# 03_-_SCHEMATIC.net
KiCad netlist of a schematic drawn in Altium Designer
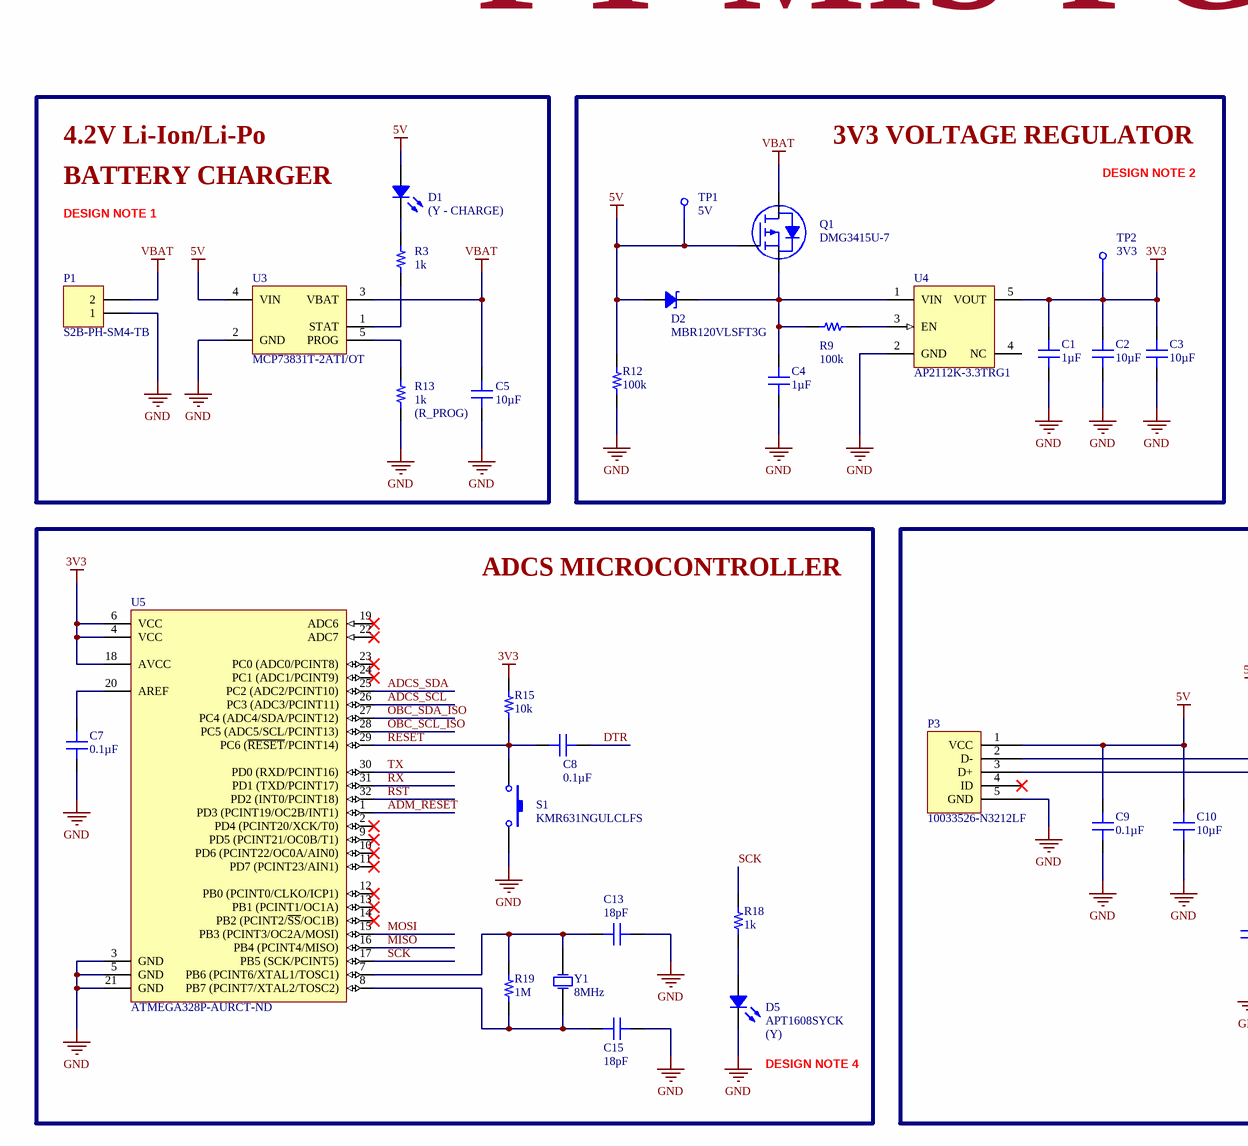
[diagram p0: [03] - SCHEMATIC.SchDoc, top left]
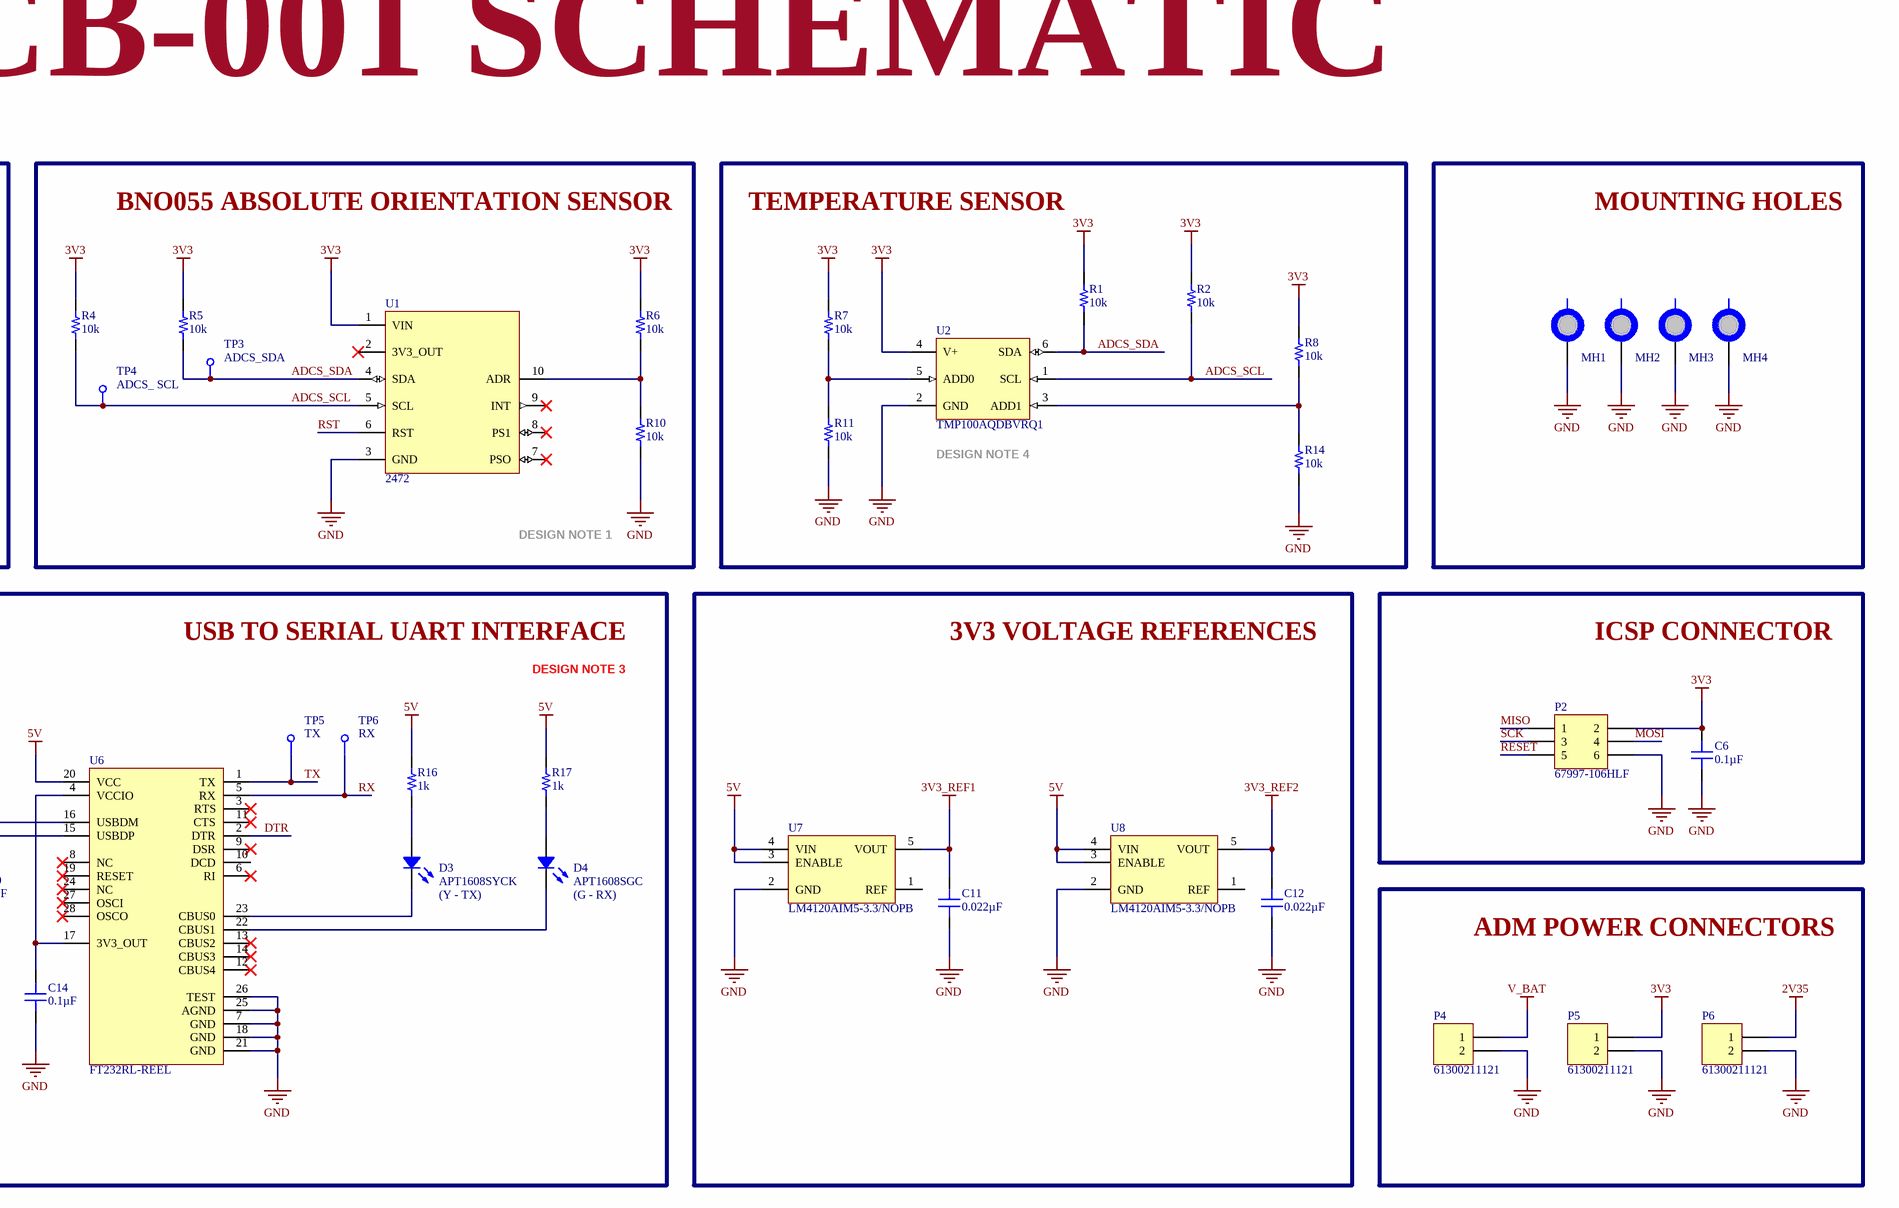
[diagram p1: [03] - SCHEMATIC.SchDoc, top right]
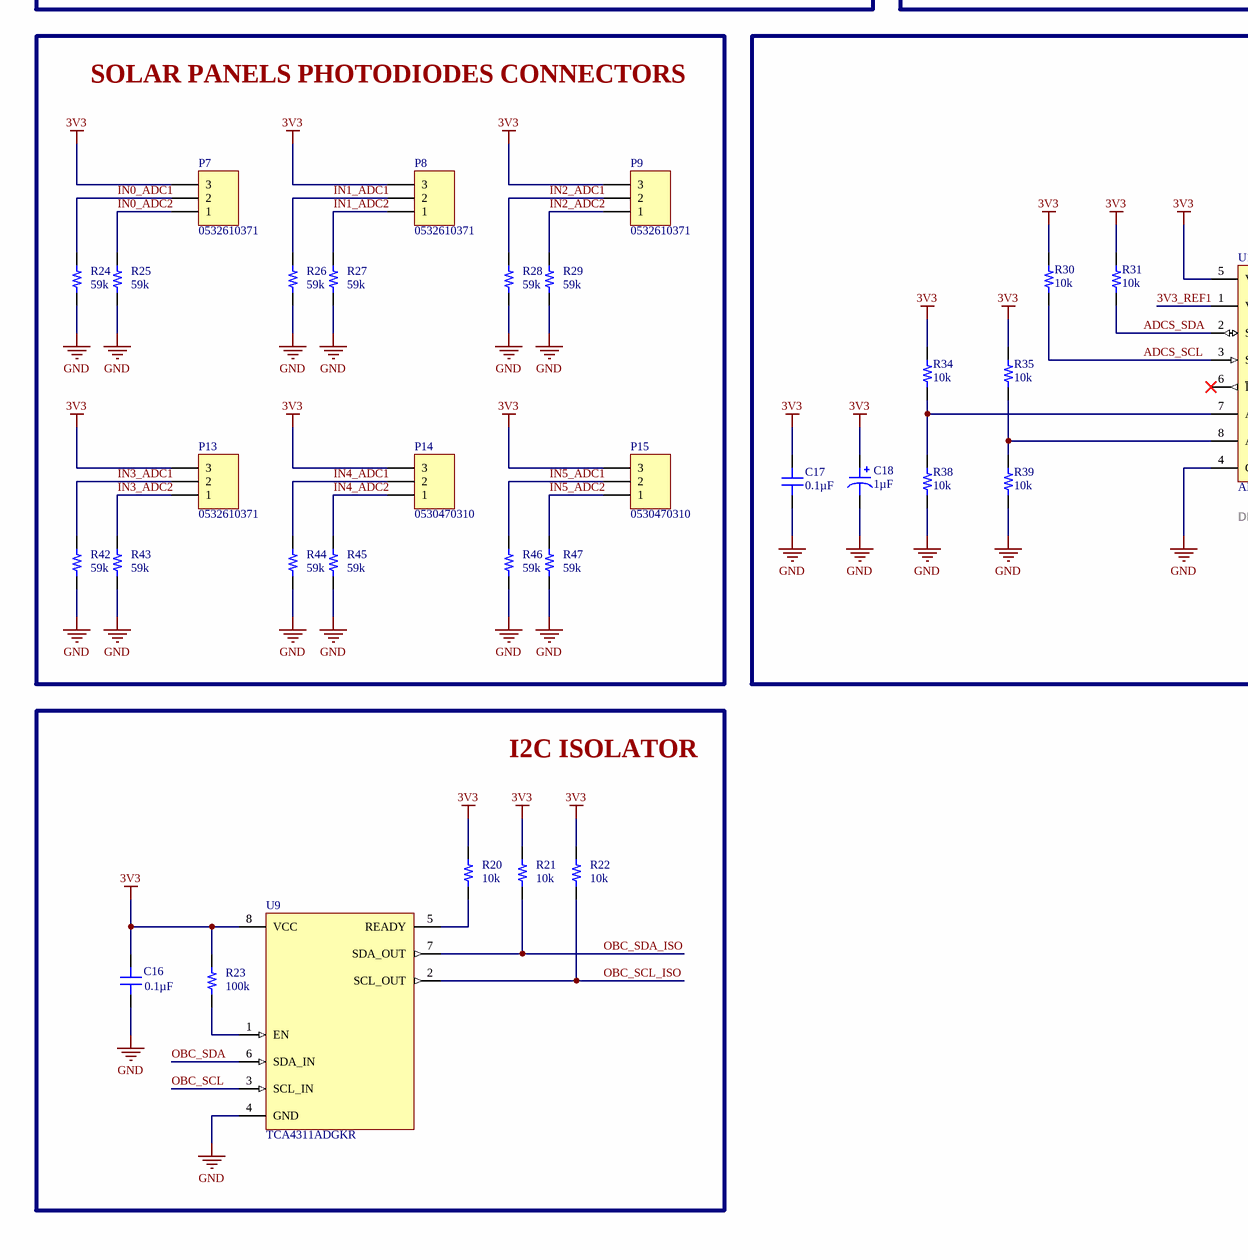
[diagram p2: [03] - SCHEMATIC.SchDoc, bottom left]
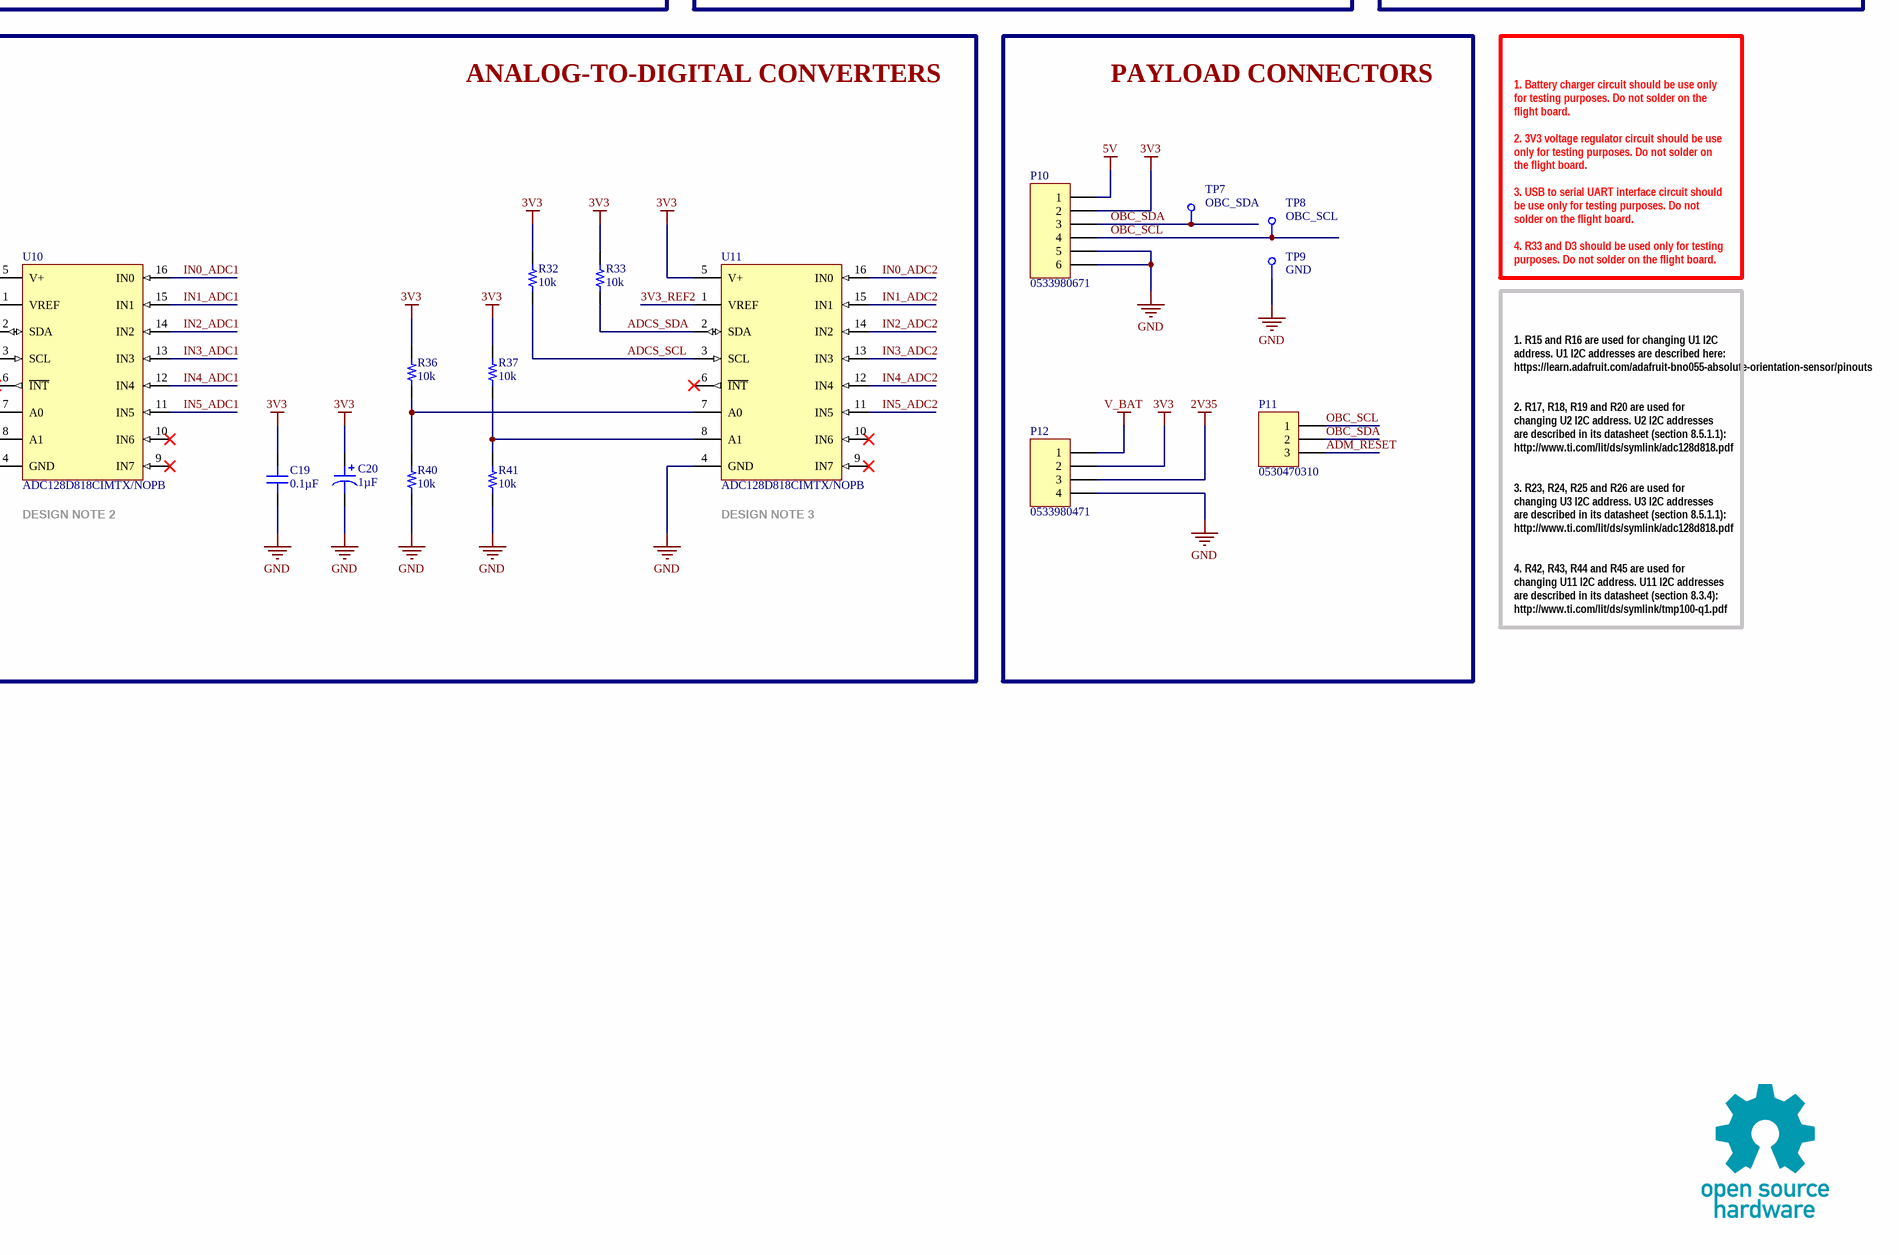
[diagram p3: [03] - SCHEMATIC.SchDoc, bottom right]

(export (version "E")
  (design (tool "Eeschema 10.0.6"))
  (components
    (comp (ref "C1")
      (value "CC0805KKX7R7BB105")
      (footprint "CAP 0805/2012")
      (description "CAP CER 1UF 16V X7R 0805")
      (fields
        (field (name "MANUFACTURER") "Yageo")
        (field (name "CAPACITANCE") "1µF")
        (field (name "TOLERANCE") "±10%")
      )
      (libsource (lib "UVG") (part "CC0805KKX7R7BB105"))
    )
    (comp (ref "C2")
      (value "LMK212BJ106KG-T")
      (footprint "CAP 0805/2012")
      (description "CAP CER 10UF 10V X5R 0805")
      (fields
        (field (name "MANUFACTURER") "Taiyo Yuden")
        (field (name "PCN PART NUMBER") "X5R, X7R Dielectrics 23/Jan/2008")
        (field (name "CAPACITANCE") "10µF")
      )
      (libsource (lib "UVG") (part "LMK212BJ106KG-T"))
    )
    (comp (ref "C3")
      (value "LMK212BJ106KG-T")
      (footprint "CAP 0805/2012")
      (description "CAP CER 10UF 10V X5R 0805")
      (fields
        (field (name "MANUFACTURER") "Taiyo Yuden")
        (field (name "PCN PART NUMBER") "X5R, X7R Dielectrics 23/Jan/2008")
        (field (name "CAPACITANCE") "10µF")
      )
      (libsource (lib "UVG") (part "LMK212BJ106KG-T"))
    )
    (comp (ref "C4")
      (value "CC0805KKX7R7BB105")
      (footprint "CAP 0805/2012")
      (description "CAP CER 1UF 16V X7R 0805")
      (fields
        (field (name "MANUFACTURER") "Yageo")
        (field (name "CAPACITANCE") "1µF")
        (field (name "TOLERANCE") "±10%")
      )
      (libsource (lib "UVG") (part "CC0805KKX7R7BB105"))
    )
    (comp (ref "C5")
      (value "LMK212BJ106KG-T")
      (footprint "CAP 0805/2012")
      (description "CAP CER 10UF 10V X5R 0805")
      (fields
        (field (name "MANUFACTURER") "Taiyo Yuden")
        (field (name "PCN PART NUMBER") "X5R, X7R Dielectrics 23/Jan/2008")
        (field (name "CAPACITANCE") "10µF")
      )
      (libsource (lib "UVG") (part "LMK212BJ106KG-T"))
    )
    (comp (ref "C6")
      (value "C2012X7R1H104K085AA")
      (footprint "CAP 0805/2012")
      (description "CAP CER 0.1UF 50V X7R 0805")
      (fields
        (field (name "MANUFACTURER") "TDK")
        (field (name "PCN PART NUMBER") "MLCC Part Number Change 30/Nov/2012")
        (field (name "CAPACITANCE") "0.1µF")
      )
      (libsource (lib "UVG") (part "C2012X7R1H104K085AA"))
    )
    (comp (ref "C7")
      (value "C2012X7R1H104K085AA")
      (footprint "CAP 0805/2012")
      (description "CAP CER 0.1UF 50V X7R 0805")
      (fields
        (field (name "MANUFACTURER") "TDK")
        (field (name "PCN PART NUMBER") "MLCC Part Number Change 30/Nov/2012")
        (field (name "CAPACITANCE") "0.1µF")
      )
      (libsource (lib "UVG") (part "C2012X7R1H104K085AA"))
    )
    (comp (ref "C8")
      (value "C2012X7R1H104K085AA")
      (footprint "CAP 0805/2012")
      (description "CAP CER 0.1UF 50V X7R 0805")
      (fields
        (field (name "MANUFACTURER") "TDK")
        (field (name "PCN PART NUMBER") "MLCC Part Number Change 30/Nov/2012")
        (field (name "CAPACITANCE") "0.1µF")
      )
      (libsource (lib "UVG") (part "C2012X7R1H104K085AA"))
    )
    (comp (ref "C9")
      (value "C0805C104Z3VACTU")
      (footprint "CAP 0805/2012")
      (description "Multilayer Ceramic Capacitors MLCC - SMD/SMT 25volts 0.1uF Y5V -20+80%")
      (fields
        (field (name "MANUFACTURER") "KEMET")
        (field (name "CAPACITANCE") "0.1µF")
        (field (name "TOLERANCE") "- 20 %, + 80 %")
      )
      (libsource (lib "UVG") (part "C0805C104Z3VACTU"))
    )
    (comp (ref "C10")
      (value "LMK212BJ106KG-T")
      (footprint "CAP 0805/2012")
      (description "CAP CER 10UF 10V X5R 0805")
      (fields
        (field (name "MANUFACTURER") "Taiyo Yuden")
        (field (name "PCN PART NUMBER") "X5R, X7R Dielectrics 23/Jan/2008")
        (field (name "CAPACITANCE") "10µF")
      )
      (libsource (lib "UVG") (part "LMK212BJ106KG-T"))
    )
    (comp (ref "C11")
      (value "GCM155R71H223KA55D")
      (footprint "CAP 0805/2012")
      (description "CAP CER 0.022UF 50V X7R 0402")
      (fields (field (name "MANUFACTURER") "Murata") (field (name "CAPACITANCE") "0.022µF"))
      (libsource (lib "UVG") (part "GCM155R71H223KA55D"))
    )
    (comp (ref "C12")
      (value "GCM155R71H223KA55D")
      (footprint "CAP 0805/2012")
      (description "CAP CER 0.022UF 50V X7R 0402")
      (fields (field (name "MANUFACTURER") "Murata") (field (name "CAPACITANCE") "0.022µF"))
      (libsource (lib "UVG") (part "GCM155R71H223KA55D"))
    )
    (comp (ref "C13")
      (value "C0805C180J5GAC-TU")
      (footprint "CAP 0805/2012")
      (description "CAP CER 18PF 50V NP0 0805")
      (fields
        (field (name "MANUFACTURER") "KEMET")
        (field (name "CAPACITANCE") "18pF")
        (field (name "VOLTAGE") "50VDC")
      )
      (libsource (lib "UVG") (part "C0805C180J5GAC-TU"))
    )
    (comp (ref "C14")
      (value "C0805C104Z3VACTU")
      (footprint "CAP 0805/2012")
      (description "Multilayer Ceramic Capacitors MLCC - SMD/SMT 25volts 0.1uF Y5V -20+80%")
      (fields
        (field (name "MANUFACTURER") "KEMET")
        (field (name "CAPACITANCE") "0.1µF")
        (field (name "TOLERANCE") "- 20 %, + 80 %")
      )
      (libsource (lib "UVG") (part "C0805C104Z3VACTU"))
    )
    (comp (ref "C15")
      (value "C0805C180J5GAC-TU")
      (footprint "CAP 0805/2012")
      (description "CAP CER 18PF 50V NP0 0805")
      (fields
        (field (name "MANUFACTURER") "KEMET")
        (field (name "CAPACITANCE") "18pF")
        (field (name "VOLTAGE") "50VDC")
      )
      (libsource (lib "UVG") (part "C0805C180J5GAC-TU"))
    )
    (comp (ref "C16")
      (value "C0805C104Z3VACTU")
      (footprint "CAP 0805/2012")
      (description "Multilayer Ceramic Capacitors MLCC - SMD/SMT 25volts 0.1uF Y5V -20+80%")
      (fields
        (field (name "MANUFACTURER") "KEMET")
        (field (name "CAPACITANCE") "0.1µF")
        (field (name "TOLERANCE") "- 20 %, + 80 %")
      )
      (libsource (lib "UVG") (part "C0805C104Z3VACTU"))
    )
    (comp (ref "C17")
      (value "C0805C104Z3VACTU")
      (footprint "CAP 0805/2012")
      (description "Multilayer Ceramic Capacitors MLCC - SMD/SMT 25volts 0.1uF Y5V -20+80%")
      (fields
        (field (name "MANUFACTURER") "KEMET")
        (field (name "CAPACITANCE") "0.1µF")
        (field (name "TOLERANCE") "- 20 %, + 80 %")
      )
      (libsource (lib "UVG") (part "C0805C104Z3VACTU"))
    )
    (comp (ref "C18")
      (value "F921C105MPA")
      (footprint "CAP 0805/2012 TANTALUM")
      (description "CAP TANT 1UF 16V 20% 0805")
      (fields (field (name "MANUFACTURER") "Kyocera AVX") (field (name "CAPACITANCE") "1µF"))
      (libsource (lib "UVG") (part "F921C105MPA"))
    )
    (comp (ref "C19")
      (value "C0805C104Z3VACTU")
      (footprint "CAP 0805/2012")
      (description "Multilayer Ceramic Capacitors MLCC - SMD/SMT 25volts 0.1uF Y5V -20+80%")
      (fields
        (field (name "MANUFACTURER") "KEMET")
        (field (name "CAPACITANCE") "0.1µF")
        (field (name "TOLERANCE") "- 20 %, + 80 %")
      )
      (libsource (lib "UVG") (part "C0805C104Z3VACTU"))
    )
    (comp (ref "C20")
      (value "F921C105MPA")
      (footprint "CAP 0805/2012 TANTALUM")
      (description "CAP TANT 1UF 16V 20% 0805")
      (fields (field (name "MANUFACTURER") "Kyocera AVX") (field (name "CAPACITANCE") "1µF"))
      (libsource (lib "UVG") (part "F921C105MPA"))
    )
    (comp (ref "D1")
      (value "APT1608SYCK")
      (footprint "LED 0603/1608 YELLOW")
      (description "LED 1.6X0.8MM 590NM YLW CLR SMD")
      (fields (field (name "MANUFACTURER") "Kingbright"))
      (libsource (lib "UVG") (part "APT1608SYCK"))
    )
    (comp (ref "D2")
      (value "MBR120VLSFT3G")
      (footprint "SOD123F")
      (description "Schottky Diodes & Rectifiers 1A 20V")
      (fields (field (name "MANUFACTURER") "ON Semiconductor"))
      (libsource (lib "UVG") (part "MBR120VLSFT3G"))
    )
    (comp (ref "D3")
      (value "APT1608SYCK")
      (footprint "LED 0603/1608 YELLOW")
      (description "LED 1.6X0.8MM 590NM YLW CLR SMD")
      (fields (field (name "MANUFACTURER") "Kingbright"))
      (libsource (lib "UVG") (part "APT1608SYCK"))
    )
    (comp (ref "D4")
      (value "APT1608SGC")
      (footprint "LED 0603/1608 GREEN")
      (description "LED 1.6X0.8MM 568NM GRN CLR SMD")
      (fields (field (name "MANUFACTURER") "Kingbright"))
      (libsource (lib "UVG") (part "APT1608SGC"))
    )
    (comp (ref "D5")
      (value "APT1608SYCK")
      (footprint "LED 0603/1608 YELLOW")
      (description "LED 1.6X0.8MM 590NM YLW CLR SMD")
      (fields (field (name "MANUFACTURER") "Kingbright"))
      (libsource (lib "UVG") (part "APT1608SYCK"))
    )
    (comp (ref "MH1")
      (value "MH_3.8MMNC_2.5MMD")
      (footprint "MH_3.8MMNC_2.5MMD_NON_COPPER_NPTH")
      (description "Mounting Hole 3.8mm Diameter (Non Copper), 2.5mm Drill NPTH")
      (libsource (lib "UVG") (part "MH_3.8MMNC_2MMD"))
    )
    (comp (ref "MH2")
      (value "MH_3.8MMNC_2.5MMD")
      (footprint "MH_3.8MMNC_2.5MMD_NON_COPPER_NPTH")
      (description "Mounting Hole 3.8mm Diameter (Non Copper), 2.5mm Drill NPTH")
      (libsource (lib "UVG") (part "MH_3.8MMNC_2MMD"))
    )
    (comp (ref "MH3")
      (value "MH_3.8MMNC_2.5MMD")
      (footprint "MH_3.8MMNC_2.5MMD_NON_COPPER_NPTH")
      (description "Mounting Hole 3.8mm Diameter (Non Copper), 2.5mm Drill NPTH")
      (libsource (lib "UVG") (part "MH_3.8MMNC_2MMD"))
    )
    (comp (ref "MH4")
      (value "MH_3.8MMNC_2.5MMD")
      (footprint "MH_3.8MMNC_2.5MMD_NON_COPPER_NPTH")
      (description "Mounting Hole 3.8mm Diameter (Non Copper), 2.5mm Drill NPTH")
      (libsource (lib "UVG") (part "MH_3.8MMNC_2MMD"))
    )
    (comp (ref "P1")
      (value "S2B-PH-SM4-TB")
      (footprint "S2B-PH-SM4-TB(LF)(SN)")
      (description "2 Positions Header, Shrouded Connector 0.079\" (2.00mm) Surface Mount, Right Angle Tin")
      (fields
        (field (name "MANUFACTURER") "JST")
        (field (name "MANUFACTURER PART NUMBER") "S2B-PH-SM4-TB(LF)(SN)")
      )
      (libsource (lib "UVG") (part "S2B-PH-SM4-TB(LF)(SN)"))
    )
    (comp (ref "P2")
      (value "67997-106HLF")
      (footprint "67997-106HLF")
      (description "6 Positions Header, Unshrouded Connector 0.100\" (2.54mm) Through Hole Gold or Gold, GXT™")
      (fields (field (name "MANUFACTURER") "Amphenol FCI"))
      (libsource (lib "UVG") (part "67997-106HLF"))
    )
    (comp (ref "P3")
      (value "10033526-N3212LF")
      (footprint "FCI USB 10033526-N3212LF")
      (description "Conn Mini USB Type B RCP 5 POS 0.8mm Solder RA SMD 5 Terminal 1 Port T/R")
      (fields (field (name "MANUFACTURER") "Amphenol FCI"))
      (libsource (lib "UVG") (part "10033526-N3212LF"))
    )
    (comp (ref "P4")
      (value "61300211121")
      (footprint "61300211121")
      (description "Headers & Wire Housings WR-PHD 2.54mm Header 2P THT")
      (fields (field (name "MANUFACTURER") "Wurth Electronics"))
      (libsource (lib "UVG") (part "61300211121"))
    )
    (comp (ref "P5")
      (value "61300211121")
      (footprint "61300211121")
      (description "Headers & Wire Housings WR-PHD 2.54mm Header 2P THT")
      (fields (field (name "MANUFACTURER") "Wurth Electronics"))
      (libsource (lib "UVG") (part "61300211121"))
    )
    (comp (ref "P6")
      (value "61300211121")
      (footprint "61300211121")
      (description "Headers & Wire Housings WR-PHD 2.54mm Header 2P THT")
      (fields (field (name "MANUFACTURER") "Wurth Electronics"))
      (libsource (lib "UVG") (part "61300211121"))
    )
    (comp (ref "P7")
      (value "0532610371")
      (footprint "0532610371")
      (description "3 Positions Header, Shrouded Connector 0.049\" (1.25mm) Surface Mount, Right Angle Tin")
      (fields (field (name "MANUFACTURER") "Molex"))
      (libsource (lib "UVG") (part "0532610371"))
    )
    (comp (ref "P8")
      (value "0532610371")
      (footprint "0532610371")
      (description "3 Positions Header, Shrouded Connector 0.049\" (1.25mm) Surface Mount, Right Angle Tin")
      (fields (field (name "MANUFACTURER") "Molex"))
      (libsource (lib "UVG") (part "0532610371"))
    )
    (comp (ref "P9")
      (value "0532610371")
      (footprint "0532610371")
      (description "3 Positions Header, Shrouded Connector 0.049\" (1.25mm) Surface Mount, Right Angle Tin")
      (fields (field (name "MANUFACTURER") "Molex"))
      (libsource (lib "UVG") (part "0532610371"))
    )
    (comp (ref "P10")
      (value "0533980671")
      (footprint "0533980671")
      (description "6 Positions Header, Shrouded Connector 0.049\" (1.25mm) Surface Mount, Right Angle Tin")
      (fields (field (name "MANUFACTURER") "Molex") (field (name "MANUFACTURER PART NUMBER") "53398-0671"))
      (libsource (lib "UVG") (part "0533980671"))
    )
    (comp (ref "P11")
      (value "0530470310")
      (footprint "0530470310")
      (description "CONN HEADER 3POS 1.25MM VERT TIN")
      (fields (field (name "MANUFACTURER") "Molex"))
      (libsource (lib "") (part "0530470310_1"))
    )
    (comp (ref "P12")
      (value "0533980471")
      (footprint "0533980471")
      (description "4 Positions Header, Shrouded Connector 0.049\" (1.25mm) Surface Mount, Right Angle Tin")
      (fields (field (name "MANUFACTURER") "Molex") (field (name "MANUFACTURER PART NUMBER") "53398-0471"))
      (libsource (lib "UVG") (part "0533980471"))
    )
    (comp (ref "P13")
      (value "0532610371")
      (footprint "0532610371")
      (description "3 Positions Header, Shrouded Connector 0.049\" (1.25mm) Surface Mount, Right Angle Tin")
      (fields (field (name "MANUFACTURER") "Molex"))
      (libsource (lib "UVG") (part "0532610371"))
    )
    (comp (ref "P14")
      (value "0530470310")
      (footprint "0530470310")
      (description "Conn Wire to Board HDR 3 POS 1.25mm Solder ST Thru-Hole PicoBlade™ Tray")
      (fields (field (name "MANUFACTURER") "Molex"))
      (libsource (lib "UVG") (part "0530470310"))
    )
    (comp (ref "P15")
      (value "0530470310")
      (footprint "0530470310")
      (description "Conn Wire to Board HDR 3 POS 1.25mm Solder ST Thru-Hole PicoBlade™ Tray")
      (fields (field (name "MANUFACTURER") "Molex"))
      (libsource (lib "UVG") (part "0530470310"))
    )
    (comp (ref "Q1")
      (value "DMG3415U-7")
      (footprint "DIODES SOT-23-3")
      (description "MOSFET P-CH 20V 4A SOT-23")
      (fields (field (name "MANUFACTURER") "Diodes"))
      (libsource (lib "UVG") (part "DMG3415U-7"))
    )
    (comp (ref "R1")
      (value "RC0805FR-0710KL")
      (footprint "RES 0805/2012")
      (description "RES SMD 10K OHM 1% 1/8W 0805")
      (fields
        (field (name "MANUFACTURER") "Yageo")
        (field (name "RESISTANCE") "10k")
        (field (name "TOLERANCE") "1 %")
      )
      (libsource (lib "UVG") (part "RC0805FR-0710KL"))
    )
    (comp (ref "R2")
      (value "RC0805FR-0710KL")
      (footprint "RES 0805/2012")
      (description "RES SMD 10K OHM 1% 1/8W 0805")
      (fields
        (field (name "MANUFACTURER") "Yageo")
        (field (name "RESISTANCE") "10k")
        (field (name "TOLERANCE") "1 %")
      )
      (libsource (lib "UVG") (part "RC0805FR-0710KL"))
    )
    (comp (ref "R3")
      (value "RNCP0805FTD1K00")
      (footprint "RES 0805/2012")
      (description "RNCP 0805 0.25W 1kO ±1% ±100ppm/°C High Power Anti-Sulfur ThinFilm Chip Resistor")
      (fields
        (field (name "MANUFACTURER") "Stackpole Electronics")
        (field (name "RESISTANCE (OHMS)") "1k")
        (field (name "TOLERANCE") "±1%")
      )
      (libsource (lib "UVG") (part "RNCP0805FTD1K00"))
    )
    (comp (ref "R4")
      (value "RR1220P-103-D")
      (footprint "RES 0805/2012")
      (description "RES SMD 10K OHM 0.5% 1/10W 0805")
      (fields
        (field (name "MANUFACTURER") "Susumu")
        (field (name "RESISTANCE") "10k")
        (field (name "TOLERANCE") "0.5 %")
      )
      (libsource (lib "UVG") (part "RR1220P-103-D"))
    )
    (comp (ref "R5")
      (value "RR1220P-103-D")
      (footprint "RES 0805/2012")
      (description "RES SMD 10K OHM 0.5% 1/10W 0805")
      (fields
        (field (name "MANUFACTURER") "Susumu")
        (field (name "RESISTANCE") "10k")
        (field (name "TOLERANCE") "0.5 %")
      )
      (libsource (lib "UVG") (part "RR1220P-103-D"))
    )
    (comp (ref "R6")
      (value "RR1220P-103-D")
      (footprint "RES 0805/2012")
      (description "RES SMD 10K OHM 0.5% 1/10W 0805")
      (fields
        (field (name "MANUFACTURER") "Susumu")
        (field (name "RESISTANCE") "10k")
        (field (name "TOLERANCE") "0.5 %")
      )
      (libsource (lib "UVG") (part "RR1220P-103-D"))
    )
    (comp (ref "R7")
      (value "RC0805FR-0710KL")
      (footprint "RES 0805/2012")
      (description "RES SMD 10K OHM 1% 1/8W 0805")
      (fields
        (field (name "MANUFACTURER") "Yageo")
        (field (name "RESISTANCE") "10k")
        (field (name "TOLERANCE") "1 %")
      )
      (libsource (lib "UVG") (part "RC0805FR-0710KL"))
    )
    (comp (ref "R8")
      (value "RC0805FR-0710KL")
      (footprint "RES 0805/2012")
      (description "RES SMD 10K OHM 1% 1/8W 0805")
      (fields
        (field (name "MANUFACTURER") "Yageo")
        (field (name "RESISTANCE") "10k")
        (field (name "TOLERANCE") "1 %")
      )
      (libsource (lib "UVG") (part "RC0805FR-0710KL"))
    )
    (comp (ref "R9")
      (value "RPC0805JT100K")
      (footprint "RES 0805/2012")
      (description "RES SMD 100K OHM 5% 1/4W 0805")
      (fields
        (field (name "MANUFACTURER") "Stackpole Electronics")
        (field (name "RESISTANCE (OHMS)") "100k")
        (field (name "TOLERANCE") "±5%")
      )
      (libsource (lib "UVG") (part "RPC0805JT100K"))
    )
    (comp (ref "R10")
      (value "RR1220P-103-D")
      (footprint "RES 0805/2012")
      (description "RES SMD 10K OHM 0.5% 1/10W 0805")
      (fields
        (field (name "MANUFACTURER") "Susumu")
        (field (name "RESISTANCE") "10k")
        (field (name "TOLERANCE") "0.5 %")
      )
      (libsource (lib "UVG") (part "RR1220P-103-D"))
    )
    (comp (ref "R11")
      (value "RC0805FR-0710KL")
      (footprint "RES 0805/2012")
      (description "RES SMD 10K OHM 1% 1/8W 0805")
      (fields
        (field (name "MANUFACTURER") "Yageo")
        (field (name "RESISTANCE") "10k")
        (field (name "TOLERANCE") "1 %")
      )
      (libsource (lib "UVG") (part "RC0805FR-0710KL"))
    )
    (comp (ref "R12")
      (value "RPC0805JT100K")
      (footprint "RES 0805/2012")
      (description "RES SMD 100K OHM 5% 1/4W 0805")
      (fields
        (field (name "MANUFACTURER") "Stackpole Electronics")
        (field (name "RESISTANCE (OHMS)") "100k")
        (field (name "TOLERANCE") "±5%")
      )
      (libsource (lib "UVG") (part "RPC0805JT100K"))
    )
    (comp (ref "R13")
      (value "RNCP0805FTD1K00")
      (footprint "RES 0805/2012")
      (description "RNCP 0805 0.25W 1kO ±1% ±100ppm/°C High Power Anti-Sulfur ThinFilm Chip Resistor")
      (fields
        (field (name "MANUFACTURER") "Stackpole Electronics")
        (field (name "RESISTANCE (OHMS)") "1k")
        (field (name "TOLERANCE") "±1%")
      )
      (libsource (lib "UVG") (part "RNCP0805FTD1K00"))
    )
    (comp (ref "R14")
      (value "RC0805FR-0710KL")
      (footprint "RES 0805/2012")
      (description "RES SMD 10K OHM 1% 1/8W 0805")
      (fields
        (field (name "MANUFACTURER") "Yageo")
        (field (name "RESISTANCE") "10k")
        (field (name "TOLERANCE") "1 %")
      )
      (libsource (lib "UVG") (part "RC0805FR-0710KL"))
    )
    (comp (ref "R15")
      (value "RC0805FR-0710KL")
      (footprint "RES 0805/2012")
      (description "RES SMD 10K OHM 1% 1/8W 0805")
      (fields
        (field (name "MANUFACTURER") "Yageo")
        (field (name "RESISTANCE") "10k")
        (field (name "TOLERANCE") "1 %")
      )
      (libsource (lib "UVG") (part "RC0805FR-0710KL"))
    )
    (comp (ref "R16")
      (value "RNCP0805FTD1K00")
      (footprint "RES 0805/2012")
      (description "RNCP 0805 0.25W 1kO ±1% ±100ppm/°C High Power Anti-Sulfur ThinFilm Chip Resistor")
      (fields
        (field (name "MANUFACTURER") "Stackpole Electronics")
        (field (name "RESISTANCE (OHMS)") "1k")
        (field (name "TOLERANCE") "±1%")
      )
      (libsource (lib "UVG") (part "RNCP0805FTD1K00"))
    )
    (comp (ref "R17")
      (value "RNCP0805FTD1K00")
      (footprint "RES 0805/2012")
      (description "RNCP 0805 0.25W 1kO ±1% ±100ppm/°C High Power Anti-Sulfur ThinFilm Chip Resistor")
      (fields
        (field (name "MANUFACTURER") "Stackpole Electronics")
        (field (name "RESISTANCE (OHMS)") "1k")
        (field (name "TOLERANCE") "±1%")
      )
      (libsource (lib "UVG") (part "RNCP0805FTD1K00"))
    )
    (comp (ref "R18")
      (value "RNCP0805FTD1K00")
      (footprint "RES 0805/2012")
      (description "RNCP 0805 0.25W 1kO ±1% ±100ppm/°C High Power Anti-Sulfur ThinFilm Chip Resistor")
      (fields
        (field (name "MANUFACTURER") "Stackpole Electronics")
        (field (name "RESISTANCE (OHMS)") "1k")
        (field (name "TOLERANCE") "±1%")
      )
      (libsource (lib "UVG") (part "RNCP0805FTD1K00"))
    )
    (comp (ref "R19")
      (value "RC0805FR-0710ML")
      (footprint "RES 0805/2012")
      (fields
        (field (name "MANUFACTURER") "Yageo")
        (field (name "RESISTANCE") "1M")
        (field (name "TOLERANCE") "1 %")
      )
      (libsource (lib "UVG") (part "RC0805FR-0710ML"))
    )
    (comp (ref "R20")
      (value "RR1220P-103-D")
      (footprint "RES 0805/2012")
      (description "RES SMD 10K OHM 0.5% 1/10W 0805")
      (fields
        (field (name "MANUFACTURER") "Susumu")
        (field (name "RESISTANCE") "10k")
        (field (name "TOLERANCE") "0.5 %")
      )
      (libsource (lib "UVG") (part "RR1220P-103-D"))
    )
    (comp (ref "R21")
      (value "RR1220P-103-D")
      (footprint "RES 0805/2012")
      (description "RES SMD 10K OHM 0.5% 1/10W 0805")
      (fields
        (field (name "MANUFACTURER") "Susumu")
        (field (name "RESISTANCE") "10k")
        (field (name "TOLERANCE") "0.5 %")
      )
      (libsource (lib "UVG") (part "RR1220P-103-D"))
    )
    (comp (ref "R22")
      (value "RR1220P-103-D")
      (footprint "RES 0805/2012")
      (description "RES SMD 10K OHM 0.5% 1/10W 0805")
      (fields
        (field (name "MANUFACTURER") "Susumu")
        (field (name "RESISTANCE") "10k")
        (field (name "TOLERANCE") "0.5 %")
      )
      (libsource (lib "UVG") (part "RR1220P-103-D"))
    )
    (comp (ref "R23")
      (value "RPC0805JT100K")
      (footprint "RES 0805/2012")
      (description "RES SMD 100K OHM 5% 1/4W 0805")
      (fields
        (field (name "MANUFACTURER") "Stackpole Electronics")
        (field (name "RESISTANCE (OHMS)") "100k")
        (field (name "TOLERANCE") "±5%")
      )
      (libsource (lib "UVG") (part "RPC0805JT100K"))
    )
    (comp (ref "R24")
      (value "ERA6AEB5902V")
      (footprint "RES 0805/2012")
      (description "RES SMD 59K OHM 0.1% 1/8W 0805")
      (fields
        (field (name "MANUFACTURER") "Panasonic")
        (field (name "RESISTANCE") "59k")
        (field (name "TOLERANCE") "0.1%")
      )
      (libsource (lib "UVG") (part "ERA6AEB5902V"))
    )
    (comp (ref "R25")
      (value "ERA6AEB5902V")
      (footprint "RES 0805/2012")
      (description "RES SMD 59K OHM 0.1% 1/8W 0805")
      (fields
        (field (name "MANUFACTURER") "Panasonic")
        (field (name "RESISTANCE") "59k")
        (field (name "TOLERANCE") "0.1%")
      )
      (libsource (lib "UVG") (part "ERA6AEB5902V"))
    )
    (comp (ref "R26")
      (value "ERA6AEB5902V")
      (footprint "RES 0805/2012")
      (description "RES SMD 59K OHM 0.1% 1/8W 0805")
      (fields
        (field (name "MANUFACTURER") "Panasonic")
        (field (name "RESISTANCE") "59k")
        (field (name "TOLERANCE") "0.1%")
      )
      (libsource (lib "UVG") (part "ERA6AEB5902V"))
    )
    (comp (ref "R27")
      (value "ERA6AEB5902V")
      (footprint "RES 0805/2012")
      (description "RES SMD 59K OHM 0.1% 1/8W 0805")
      (fields
        (field (name "MANUFACTURER") "Panasonic")
        (field (name "RESISTANCE") "59k")
        (field (name "TOLERANCE") "0.1%")
      )
      (libsource (lib "UVG") (part "ERA6AEB5902V"))
    )
    (comp (ref "R28")
      (value "ERA6AEB5902V")
      (footprint "RES 0805/2012")
      (description "RES SMD 59K OHM 0.1% 1/8W 0805")
      (fields
        (field (name "MANUFACTURER") "Panasonic")
        (field (name "RESISTANCE") "59k")
        (field (name "TOLERANCE") "0.1%")
      )
      (libsource (lib "UVG") (part "ERA6AEB5902V"))
    )
    (comp (ref "R29")
      (value "ERA6AEB5902V")
      (footprint "RES 0805/2012")
      (description "RES SMD 59K OHM 0.1% 1/8W 0805")
      (fields
        (field (name "MANUFACTURER") "Panasonic")
        (field (name "RESISTANCE") "59k")
        (field (name "TOLERANCE") "0.1%")
      )
      (libsource (lib "UVG") (part "ERA6AEB5902V"))
    )
    (comp (ref "R30")
      (value "RR1220P-103-D")
      (footprint "RES 0805/2012")
      (description "RES SMD 10K OHM 0.5% 1/10W 0805")
      (fields
        (field (name "MANUFACTURER") "Susumu")
        (field (name "RESISTANCE") "10k")
        (field (name "TOLERANCE") "0.5 %")
      )
      (libsource (lib "UVG") (part "RR1220P-103-D"))
    )
    (comp (ref "R31")
      (value "RR1220P-103-D")
      (footprint "RES 0805/2012")
      (description "RES SMD 10K OHM 0.5% 1/10W 0805")
      (fields
        (field (name "MANUFACTURER") "Susumu")
        (field (name "RESISTANCE") "10k")
        (field (name "TOLERANCE") "0.5 %")
      )
      (libsource (lib "UVG") (part "RR1220P-103-D"))
    )
    (comp (ref "R32")
      (value "RR1220P-103-D")
      (footprint "RES 0805/2012")
      (description "RES SMD 10K OHM 0.5% 1/10W 0805")
      (fields
        (field (name "MANUFACTURER") "Susumu")
        (field (name "RESISTANCE") "10k")
        (field (name "TOLERANCE") "0.5 %")
      )
      (libsource (lib "UVG") (part "RR1220P-103-D"))
    )
    (comp (ref "R33")
      (value "RR1220P-103-D")
      (footprint "RES 0805/2012")
      (description "RES SMD 10K OHM 0.5% 1/10W 0805")
      (fields
        (field (name "MANUFACTURER") "Susumu")
        (field (name "RESISTANCE") "10k")
        (field (name "TOLERANCE") "0.5 %")
      )
      (libsource (lib "UVG") (part "RR1220P-103-D"))
    )
    (comp (ref "R34")
      (value "RR1220P-103-D")
      (footprint "RES 0805/2012")
      (description "RES SMD 10K OHM 0.5% 1/10W 0805")
      (fields
        (field (name "MANUFACTURER") "Susumu")
        (field (name "RESISTANCE") "10k")
        (field (name "TOLERANCE") "0.5 %")
      )
      (libsource (lib "UVG") (part "RR1220P-103-D"))
    )
    (comp (ref "R35")
      (value "RR1220P-103-D")
      (footprint "RES 0805/2012")
      (description "RES SMD 10K OHM 0.5% 1/10W 0805")
      (fields
        (field (name "MANUFACTURER") "Susumu")
        (field (name "RESISTANCE") "10k")
        (field (name "TOLERANCE") "0.5 %")
      )
      (libsource (lib "UVG") (part "RR1220P-103-D"))
    )
    (comp (ref "R36")
      (value "RR1220P-103-D")
      (footprint "RES 0805/2012")
      (description "RES SMD 10K OHM 0.5% 1/10W 0805")
      (fields
        (field (name "MANUFACTURER") "Susumu")
        (field (name "RESISTANCE") "10k")
        (field (name "TOLERANCE") "0.5 %")
      )
      (libsource (lib "UVG") (part "RR1220P-103-D"))
    )
    (comp (ref "R37")
      (value "RR1220P-103-D")
      (footprint "RES 0805/2012")
      (description "RES SMD 10K OHM 0.5% 1/10W 0805")
      (fields
        (field (name "MANUFACTURER") "Susumu")
        (field (name "RESISTANCE") "10k")
        (field (name "TOLERANCE") "0.5 %")
      )
      (libsource (lib "UVG") (part "RR1220P-103-D"))
    )
    (comp (ref "R38")
      (value "RR1220P-103-D")
      (footprint "RES 0805/2012")
      (description "RES SMD 10K OHM 0.5% 1/10W 0805")
      (fields
        (field (name "MANUFACTURER") "Susumu")
        (field (name "RESISTANCE") "10k")
        (field (name "TOLERANCE") "0.5 %")
      )
      (libsource (lib "UVG") (part "RR1220P-103-D"))
    )
    (comp (ref "R39")
      (value "RR1220P-103-D")
      (footprint "RES 0805/2012")
      (description "RES SMD 10K OHM 0.5% 1/10W 0805")
      (fields
        (field (name "MANUFACTURER") "Susumu")
        (field (name "RESISTANCE") "10k")
        (field (name "TOLERANCE") "0.5 %")
      )
      (libsource (lib "UVG") (part "RR1220P-103-D"))
    )
    (comp (ref "R40")
      (value "RR1220P-103-D")
      (footprint "RES 0805/2012")
      (description "RES SMD 10K OHM 0.5% 1/10W 0805")
      (fields
        (field (name "MANUFACTURER") "Susumu")
        (field (name "RESISTANCE") "10k")
        (field (name "TOLERANCE") "0.5 %")
      )
      (libsource (lib "UVG") (part "RR1220P-103-D"))
    )
    (comp (ref "R41")
      (value "RR1220P-103-D")
      (footprint "RES 0805/2012")
      (description "RES SMD 10K OHM 0.5% 1/10W 0805")
      (fields
        (field (name "MANUFACTURER") "Susumu")
        (field (name "RESISTANCE") "10k")
        (field (name "TOLERANCE") "0.5 %")
      )
      (libsource (lib "UVG") (part "RR1220P-103-D"))
    )
    (comp (ref "R42")
      (value "ERA6AEB5902V")
      (footprint "RES 0805/2012")
      (description "RES SMD 59K OHM 0.1% 1/8W 0805")
      (fields
        (field (name "MANUFACTURER") "Panasonic")
        (field (name "RESISTANCE") "59k")
        (field (name "TOLERANCE") "0.1%")
      )
      (libsource (lib "UVG") (part "ERA6AEB5902V"))
    )
    (comp (ref "R43")
      (value "ERA6AEB5902V")
      (footprint "RES 0805/2012")
      (description "RES SMD 59K OHM 0.1% 1/8W 0805")
      (fields
        (field (name "MANUFACTURER") "Panasonic")
        (field (name "RESISTANCE") "59k")
        (field (name "TOLERANCE") "0.1%")
      )
      (libsource (lib "UVG") (part "ERA6AEB5902V"))
    )
    (comp (ref "R44")
      (value "ERA6AEB5902V")
      (footprint "RES 0805/2012")
      (description "RES SMD 59K OHM 0.1% 1/8W 0805")
      (fields
        (field (name "MANUFACTURER") "Panasonic")
        (field (name "RESISTANCE") "59k")
        (field (name "TOLERANCE") "0.1%")
      )
      (libsource (lib "UVG") (part "ERA6AEB5902V"))
    )
    (comp (ref "R45")
      (value "ERA6AEB5902V")
      (footprint "RES 0805/2012")
      (description "RES SMD 59K OHM 0.1% 1/8W 0805")
      (fields
        (field (name "MANUFACTURER") "Panasonic")
        (field (name "RESISTANCE") "59k")
        (field (name "TOLERANCE") "0.1%")
      )
      (libsource (lib "UVG") (part "ERA6AEB5902V"))
    )
    (comp (ref "R46")
      (value "ERA6AEB5902V")
      (footprint "RES 0805/2012")
      (description "RES SMD 59K OHM 0.1% 1/8W 0805")
      (fields
        (field (name "MANUFACTURER") "Panasonic")
        (field (name "RESISTANCE") "59k")
        (field (name "TOLERANCE") "0.1%")
      )
      (libsource (lib "UVG") (part "ERA6AEB5902V"))
    )
    (comp (ref "R47")
      (value "ERA6AEB5902V")
      (footprint "RES 0805/2012")
      (description "RES SMD 59K OHM 0.1% 1/8W 0805")
      (fields
        (field (name "MANUFACTURER") "Panasonic")
        (field (name "RESISTANCE") "59k")
        (field (name "TOLERANCE") "0.1%")
      )
      (libsource (lib "UVG") (part "ERA6AEB5902V"))
    )
    (comp (ref "S1")
      (value "KMR631NGULCLFS")
      (footprint "KMR631NGLFS")
      (description "SWITCH TACTILE SPST-NO 50MA 32V")
      (fields (field (name "MANUFACTURER") "ITT C&K"))
      (libsource (lib "UVG") (part "KMR631NGULCLFS"))
    )
    (comp (ref "TP1") (value "5V") (footprint "Testpoint") (libsource (lib "UVG") (part "Testpoint")))
    (comp (ref "TP2") (value "3V3") (footprint "Testpoint") (libsource (lib "UVG") (part "Testpoint")))
    (comp (ref "TP3") (value "ADCS_SDA") (footprint "Testpoint") (libsource (lib "UVG") (part "Testpoint")))
    (comp (ref "TP4") (value "ADCS_ SCL") (footprint "Testpoint") (libsource (lib "UVG") (part "Testpoint")))
    (comp (ref "TP5") (value "TX") (footprint "Testpoint") (libsource (lib "UVG") (part "Testpoint")))
    (comp (ref "TP6") (value "RX") (footprint "Testpoint") (libsource (lib "UVG") (part "Testpoint")))
    (comp (ref "TP7") (value "OBC_SDA") (footprint "Testpoint") (libsource (lib "UVG") (part "Testpoint")))
    (comp (ref "TP8") (value "OBC_SCL") (footprint "Testpoint") (libsource (lib "UVG") (part "Testpoint")))
    (comp (ref "TP9") (value "GND") (footprint "Testpoint") (libsource (lib "UVG") (part "Testpoint")))
    (comp (ref "U1")
      (value "2472")
      (footprint "ADAFRUIT BNO055")
      (description "A 9-DOF A O IMU F B - BNO055")
      (fields
        (field (name "MANUFACTURER") "Adafruit Industries")
        (field (name "UTILIZED IC / PART") "BNO055")
      )
      (libsource (lib "UVG") (part "2472"))
    )
    (comp (ref "U2")
      (value "TMP100AQDBVRQ1")
      (footprint "SOT95P245X145-6N")
      (description "SENSOR DIGITAL -55C-125C SOT23-6")
      (fields (field (name "MANUFACTURER") "Texas Instruments"))
      (libsource (lib "UVG") (part "TMP100AQDBVRQ1"))
    )
    (comp (ref "U3")
      (value "MCP73831T-2ATI/OT")
      (footprint "SOT95P245X110-5N")
      (fields (field (name "MANUFACTURER") "Microchip"))
      (libsource (lib "UVG") (part "MCP73831T-2ATI/OT"))
    )
    (comp (ref "U4")
      (value "AP2112K-3.3TRG1")
      (footprint "DIODES SOT-23-5 W5")
      (description "IC REG LDO 3.3V 0.6A SOT25")
      (fields (field (name "MANUFACTURER") "Diodes"))
      (libsource (lib "UVG") (part "AP2112K-3.3TRG1"))
    )
    (comp (ref "U5")
      (value "ATMEGA328P-AURCT-ND")
      (footprint "32A_L")
      (description "MCU 8-bit ATmega AVR RISC 32KB Flash 2.5V/3.3V/5V 32-Pin TQFP T/R")
      (fields
        (field (name "MANUFACTURER") "Microchip / Atmel")
        (field (name "MANUFACTURER PART NUMBER") "ATMEGA328P-AUR")
      )
      (libsource (lib "UVG") (part "ATMEGA328P-AUR"))
    )
    (comp (ref "U6")
      (value "FT232RL-REEL")
      (footprint "SOP65P790X200-28N")
      (description "IC USB FS SERIAL UART 28-SSOP")
      (fields (field (name "MANUFACTURER") "FTDI") (field (name "VOLTAGE") "5V"))
      (libsource (lib "UVG") (part "FT232RL-REEL"))
    )
    (comp (ref "U7")
      (value "LM4120AIM5-3.3/NOPB")
      (footprint "SOT95P245X110-5N")
      (description "TEXAS INSTRUMENTS   LM4120AIM5-3.3/NOPB   VOLTAGE REF, SERIES, 3.3V, SOT-23-5")
      (fields (field (name "MANUFACTURER") "Texas Instruments") (field (name "TOLERANCE") "0.2%"))
      (libsource (lib "UVG") (part "LM4120AIM5-3.3/NOPB"))
    )
    (comp (ref "U8")
      (value "LM4120AIM5-3.3/NOPB")
      (footprint "SOT95P245X110-5N")
      (description "TEXAS INSTRUMENTS   LM4120AIM5-3.3/NOPB   VOLTAGE REF, SERIES, 3.3V, SOT-23-5")
      (fields (field (name "MANUFACTURER") "Texas Instruments") (field (name "TOLERANCE") "0.2%"))
      (libsource (lib "UVG") (part "LM4120AIM5-3.3/NOPB"))
    )
    (comp (ref "U9")
      (value "TCA4311ADGKR")
      (footprint "8-MSOP")
      (description "IC REDRIVER I2C HOTSWAP 8VSSOP")
      (fields (field (name "MANUFACTURER") "Texas Instruments"))
      (libsource (lib "UVG") (part "TCA4311ADGKR"))
    )
    (comp (ref "U10")
      (value "ADC128D818CIMTX/NOPB")
      (footprint "TSOP65P640X120-16N")
      (description "Analog to Digital Converters - ADC")
      (fields (field (name "MANUFACTURER") "TI National Semiconductor"))
      (libsource (lib "UVG") (part "ADC128D818CIMTX/NOPB"))
    )
    (comp (ref "U11")
      (value "ADC128D818CIMTX/NOPB")
      (footprint "TSOP65P640X120-16N")
      (description "Analog to Digital Converters - ADC")
      (fields (field (name "MANUFACTURER") "TI National Semiconductor"))
      (libsource (lib "UVG") (part "ADC128D818CIMTX/NOPB"))
    )
    (comp (ref "Y1")
      (value "8MHz")
      (footprint "ABM7-16.000MHZ-D2Y-T")
      (description "CRYSTAL 8.0000MHZ 18PF SMD")
      (fields
        (field (name "MANUFACTURER") "Abracon")
        (field (name "MANUFACTURER PART NUMBER") "ABM7-8.000MHZ-D2Y-T")
      )
      (libsource (lib "UVG") (part "ABM7-8.000MHZ-D2Y-T"))
    )
  )
  (nets
    (net (code "1") (name "/ADCS_SCL") (class "Default")
      (node (ref "R2") (pin "1") (pinfunction "1_1") (pintype "passive"))
      (node (ref "R30") (pin "2") (pinfunction "2_2") (pintype "passive"))
      (node (ref "R32") (pin "2") (pinfunction "2_2") (pintype "passive"))
      (node (ref "R4") (pin "2") (pinfunction "2_2") (pintype "passive"))
      (node (ref "TP4") (pin "1") (pinfunction "1_1") (pintype "passive"))
      (node (ref "U1") (pin "5") (pinfunction "SCL_5") (pintype "input"))
      (node (ref "U10") (pin "3") (pinfunction "SCL_3") (pintype "input"))
      (node (ref "U11") (pin "3") (pinfunction "SCL_3") (pintype "input"))
      (node (ref "U2") (pin "1") (pinfunction "SCL_1") (pintype "input"))
      (node (ref "U5") (pin "26") (pinfunction "PC3_(ADC3/PCINT11)_26") (pintype "bidirectional"))
    )
    (net (code "2") (name "/ADCS_SDA") (class "Default")
      (node (ref "R1") (pin "1") (pinfunction "1_1") (pintype "passive"))
      (node (ref "R31") (pin "2") (pinfunction "2_2") (pintype "passive"))
      (node (ref "R33") (pin "2") (pinfunction "2_2") (pintype "passive"))
      (node (ref "R5") (pin "2") (pinfunction "2_2") (pintype "passive"))
      (node (ref "TP3") (pin "1") (pinfunction "1_1") (pintype "passive"))
      (node (ref "U1") (pin "4") (pinfunction "SDA_4") (pintype "bidirectional"))
      (node (ref "U10") (pin "2") (pinfunction "SDA_2") (pintype "bidirectional"))
      (node (ref "U11") (pin "2") (pinfunction "SDA_2") (pintype "bidirectional"))
      (node (ref "U2") (pin "6") (pinfunction "SDA_6") (pintype "bidirectional"))
      (node (ref "U5") (pin "25") (pinfunction "PC2_(ADC2/PCINT10)_25") (pintype "bidirectional"))
    )
    (net (code "3") (name "/ADM_RESET") (class "Default")
      (node (ref "P11") (pin "3") (pinfunction "3_3") (pintype "passive"))
      (node (ref "U5") (pin "1") (pinfunction "PD3_(PCINT19/OC2B/INT1)_1") (pintype "bidirectional"))
    )
    (net (code "4") (name "/DTR") (class "Default")
      (node (ref "C8") (pin "1") (pinfunction "1_1") (pintype "passive"))
      (node (ref "U6") (pin "2") (pinfunction "DTR_2") (pintype "passive"))
    )
    (net (code "5") (name "/IN0_ADC1") (class "Default")
      (node (ref "P7") (pin "2") (pinfunction "2_2") (pintype "passive"))
      (node (ref "R24") (pin "2") (pinfunction "2_2") (pintype "passive"))
      (node (ref "U10") (pin "16") (pinfunction "IN0_16") (pintype "input"))
    )
    (net (code "6") (name "/IN0_ADC2") (class "Default")
      (node (ref "P7") (pin "1") (pinfunction "1_1") (pintype "passive"))
      (node (ref "R25") (pin "2") (pinfunction "2_2") (pintype "passive"))
      (node (ref "U11") (pin "16") (pinfunction "IN0_16") (pintype "input"))
    )
    (net (code "7") (name "/IN1_ADC1") (class "Default")
      (node (ref "P8") (pin "2") (pinfunction "2_2") (pintype "passive"))
      (node (ref "R26") (pin "2") (pinfunction "2_2") (pintype "passive"))
      (node (ref "U10") (pin "15") (pinfunction "IN1_15") (pintype "input"))
    )
    (net (code "8") (name "/IN1_ADC2") (class "Default")
      (node (ref "P8") (pin "1") (pinfunction "1_1") (pintype "passive"))
      (node (ref "R27") (pin "2") (pinfunction "2_2") (pintype "passive"))
      (node (ref "U11") (pin "15") (pinfunction "IN1_15") (pintype "input"))
    )
    (net (code "9") (name "/IN2_ADC1") (class "Default")
      (node (ref "P9") (pin "2") (pinfunction "2_2") (pintype "passive"))
      (node (ref "R28") (pin "2") (pinfunction "2_2") (pintype "passive"))
      (node (ref "U10") (pin "14") (pinfunction "IN2_14") (pintype "input"))
    )
    (net (code "10") (name "/IN2_ADC2") (class "Default")
      (node (ref "P9") (pin "1") (pinfunction "1_1") (pintype "passive"))
      (node (ref "R29") (pin "2") (pinfunction "2_2") (pintype "passive"))
      (node (ref "U11") (pin "14") (pinfunction "IN2_14") (pintype "input"))
    )
    (net (code "11") (name "/IN3_ADC1") (class "Default")
      (node (ref "P13") (pin "2") (pinfunction "2_2") (pintype "passive"))
      (node (ref "R42") (pin "2") (pinfunction "2_2") (pintype "passive"))
      (node (ref "U10") (pin "13") (pinfunction "IN3_13") (pintype "input"))
    )
    (net (code "12") (name "/IN3_ADC2") (class "Default")
      (node (ref "P13") (pin "1") (pinfunction "1_1") (pintype "passive"))
      (node (ref "R43") (pin "2") (pinfunction "2_2") (pintype "passive"))
      (node (ref "U11") (pin "13") (pinfunction "IN3_13") (pintype "input"))
    )
    (net (code "13") (name "/IN4_ADC1") (class "Default")
      (node (ref "P14") (pin "2") (pinfunction "2_2") (pintype "passive"))
      (node (ref "R44") (pin "2") (pinfunction "2_2") (pintype "passive"))
      (node (ref "U10") (pin "12") (pinfunction "IN4_12") (pintype "input"))
    )
    (net (code "14") (name "/IN4_ADC2") (class "Default")
      (node (ref "P14") (pin "1") (pinfunction "1_1") (pintype "passive"))
      (node (ref "R45") (pin "2") (pinfunction "2_2") (pintype "passive"))
      (node (ref "U11") (pin "12") (pinfunction "IN4_12") (pintype "input"))
    )
    (net (code "15") (name "/IN5_ADC1") (class "Default")
      (node (ref "P15") (pin "2") (pinfunction "2_2") (pintype "passive"))
      (node (ref "R46") (pin "2") (pinfunction "2_2") (pintype "passive"))
      (node (ref "U10") (pin "11") (pinfunction "IN5_11") (pintype "input"))
    )
    (net (code "16") (name "/IN5_ADC2") (class "Default")
      (node (ref "P15") (pin "1") (pinfunction "1_1") (pintype "passive"))
      (node (ref "R47") (pin "2") (pinfunction "2_2") (pintype "passive"))
      (node (ref "U11") (pin "11") (pinfunction "IN5_11") (pintype "input"))
    )
    (net (code "17") (name "/MISO") (class "Default")
      (node (ref "P2") (pin "1") (pinfunction "1_1") (pintype "passive"))
      (node (ref "U5") (pin "16") (pinfunction "PB4_(PCINT4/MISO)_16") (pintype "bidirectional"))
    )
    (net (code "18") (name "/MOSI") (class "Default")
      (node (ref "P2") (pin "4") (pinfunction "4_4") (pintype "passive"))
      (node (ref "U5") (pin "15") (pinfunction "PB3_(PCINT3/OC2A/MOSI)_15") (pintype "bidirectional"))
    )
    (net (code "19") (name "/OBC_SCL") (class "Default")
      (node (ref "P10") (pin "4") (pinfunction "4_4") (pintype "passive"))
      (node (ref "P11") (pin "1") (pinfunction "1_1") (pintype "passive"))
      (node (ref "TP8") (pin "1") (pinfunction "1_1") (pintype "passive"))
      (node (ref "U9") (pin "3") (pinfunction "SCL_IN_3") (pintype "input"))
    )
    (net (code "20") (name "/OBC_SCL_ISO") (class "Default")
      (node (ref "R22") (pin "1") (pinfunction "1_1") (pintype "passive"))
      (node (ref "U5") (pin "28") (pinfunction "PC5_(ADC5/SCL/PCINT13)_28") (pintype "bidirectional"))
      (node (ref "U9") (pin "2") (pinfunction "SCL_OUT_2") (pintype "output"))
    )
    (net (code "21") (name "/OBC_SDA") (class "Default")
      (node (ref "P10") (pin "3") (pinfunction "3_3") (pintype "passive"))
      (node (ref "P11") (pin "2") (pinfunction "2_2") (pintype "passive"))
      (node (ref "TP7") (pin "1") (pinfunction "1_1") (pintype "passive"))
      (node (ref "U9") (pin "6") (pinfunction "SDA_IN_6") (pintype "input"))
    )
    (net (code "22") (name "/OBC_SDA_ISO") (class "Default")
      (node (ref "R21") (pin "1") (pinfunction "1_1") (pintype "passive"))
      (node (ref "U5") (pin "27") (pinfunction "PC4_(ADC4/SDA/PCINT12)_27") (pintype "bidirectional"))
      (node (ref "U9") (pin "7") (pinfunction "SDA_OUT_7") (pintype "output"))
    )
    (net (code "23") (name "/RESET") (class "Default")
      (node (ref "C8") (pin "2") (pinfunction "2_2") (pintype "passive"))
      (node (ref "P2") (pin "5") (pinfunction "5_5") (pintype "passive"))
      (node (ref "R15") (pin "1") (pinfunction "1_1") (pintype "passive"))
      (node (ref "S1") (pin "1") (pinfunction "1_1") (pintype "passive"))
      (node (ref "U5") (pin "29") (pinfunction "PC6_(~{RESET}/PCINT14)_29") (pintype "bidirectional"))
    )
    (net (code "24") (name "/RST") (class "Default")
      (node (ref "U1") (pin "6") (pinfunction "RST_6") (pintype "passive"))
      (node (ref "U5") (pin "32") (pinfunction "PD2_(INT0/PCINT18)_32") (pintype "bidirectional"))
    )
    (net (code "25") (name "/RX") (class "Default")
      (node (ref "TP6") (pin "1") (pinfunction "1_1") (pintype "passive"))
      (node (ref "U5") (pin "31") (pinfunction "PD1_(TXD/PCINT17)_31") (pintype "bidirectional"))
      (node (ref "U6") (pin "5") (pinfunction "RX_5") (pintype "passive"))
    )
    (net (code "26") (name "/SCK") (class "Default")
      (node (ref "P2") (pin "3") (pinfunction "3_3") (pintype "passive"))
      (node (ref "R18") (pin "1") (pinfunction "1_1") (pintype "passive"))
      (node (ref "U5") (pin "17") (pinfunction "PB5_(SCK/PCINT5)_17") (pintype "bidirectional"))
    )
    (net (code "27") (name "/TX") (class "Default")
      (node (ref "TP5") (pin "1") (pinfunction "1_1") (pintype "passive"))
      (node (ref "U5") (pin "30") (pinfunction "PD0_(RXD/PCINT16)_30") (pintype "bidirectional"))
      (node (ref "U6") (pin "1") (pinfunction "TX_1") (pintype "passive"))
    )
    (net (code "28") (name "2V35") (class "Default")
      (node (ref "P12") (pin "3") (pinfunction "3_3") (pintype "passive"))
      (node (ref "P6") (pin "1") (pinfunction "1_1") (pintype "passive"))
    )
    (net (code "29") (name "3V3") (class "Default")
      (node (ref "C1") (pin "1") (pinfunction "1_1") (pintype "passive"))
      (node (ref "C16") (pin "2") (pinfunction "2_2") (pintype "passive"))
      (node (ref "C17") (pin "2") (pinfunction "2_2") (pintype "passive"))
      (node (ref "C18") (pin "1") (pinfunction "1_1") (pintype "passive"))
      (node (ref "C19") (pin "2") (pinfunction "2_2") (pintype "passive"))
      (node (ref "C2") (pin "2") (pinfunction "2_2") (pintype "passive"))
      (node (ref "C20") (pin "1") (pinfunction "1_1") (pintype "passive"))
      (node (ref "C3") (pin "2") (pinfunction "2_2") (pintype "passive"))
      (node (ref "C6") (pin "2") (pinfunction "2_2") (pintype "passive"))
      (node (ref "P10") (pin "2") (pinfunction "2_2") (pintype "passive"))
      (node (ref "P12") (pin "2") (pinfunction "2_2") (pintype "passive"))
      (node (ref "P13") (pin "3") (pinfunction "3_3") (pintype "passive"))
      (node (ref "P14") (pin "3") (pinfunction "3_3") (pintype "passive"))
      (node (ref "P15") (pin "3") (pinfunction "3_3") (pintype "passive"))
      (node (ref "P2") (pin "2") (pinfunction "2_2") (pintype "passive"))
      (node (ref "P5") (pin "1") (pinfunction "1_1") (pintype "passive"))
      (node (ref "P7") (pin "3") (pinfunction "3_3") (pintype "passive"))
      (node (ref "P8") (pin "3") (pinfunction "3_3") (pintype "passive"))
      (node (ref "P9") (pin "3") (pinfunction "3_3") (pintype "passive"))
      (node (ref "R1") (pin "2") (pinfunction "2_2") (pintype "passive"))
      (node (ref "R15") (pin "2") (pinfunction "2_2") (pintype "passive"))
      (node (ref "R2") (pin "2") (pinfunction "2_2") (pintype "passive"))
      (node (ref "R20") (pin "2") (pinfunction "2_2") (pintype "passive"))
      (node (ref "R21") (pin "2") (pinfunction "2_2") (pintype "passive"))
      (node (ref "R22") (pin "2") (pinfunction "2_2") (pintype "passive"))
      (node (ref "R23") (pin "2") (pinfunction "2_2") (pintype "passive"))
      (node (ref "R30") (pin "1") (pinfunction "1_1") (pintype "passive"))
      (node (ref "R31") (pin "1") (pinfunction "1_1") (pintype "passive"))
      (node (ref "R32") (pin "1") (pinfunction "1_1") (pintype "passive"))
      (node (ref "R33") (pin "1") (pinfunction "1_1") (pintype "passive"))
      (node (ref "R34") (pin "2") (pinfunction "2_2") (pintype "passive"))
      (node (ref "R35") (pin "2") (pinfunction "2_2") (pintype "passive"))
      (node (ref "R36") (pin "2") (pinfunction "2_2") (pintype "passive"))
      (node (ref "R37") (pin "2") (pinfunction "2_2") (pintype "passive"))
      (node (ref "R4") (pin "1") (pinfunction "1_1") (pintype "passive"))
      (node (ref "R5") (pin "1") (pinfunction "1_1") (pintype "passive"))
      (node (ref "R6") (pin "1") (pinfunction "1_1") (pintype "passive"))
      (node (ref "R7") (pin "2") (pinfunction "2_2") (pintype "passive"))
      (node (ref "R8") (pin "2") (pinfunction "2_2") (pintype "passive"))
      (node (ref "TP2") (pin "1") (pinfunction "1_1") (pintype "passive"))
      (node (ref "U1") (pin "1") (pinfunction "VIN_1") (pintype "power_in"))
      (node (ref "U10") (pin "5") (pinfunction "V+_5") (pintype "power_in"))
      (node (ref "U11") (pin "5") (pinfunction "V+_5") (pintype "power_in"))
      (node (ref "U2") (pin "4") (pinfunction "V+_4") (pintype "power_in"))
      (node (ref "U4") (pin "5") (pinfunction "VOUT_5") (pintype "power_in"))
      (node (ref "U5") (pin "18") (pinfunction "AVCC_18") (pintype "power_in"))
      (node (ref "U5") (pin "4") (pinfunction "VCC_4") (pintype "power_in"))
      (node (ref "U5") (pin "6") (pinfunction "VCC_6") (pintype "power_in"))
      (node (ref "U9") (pin "8") (pinfunction "VCC_8") (pintype "power_in"))
    )
    (net (code "30") (name "3V3_REF1") (class "Default")
      (node (ref "C11") (pin "1") (pinfunction "1_1") (pintype "passive"))
      (node (ref "U10") (pin "1") (pinfunction "VREF_1") (pintype "power_in"))
      (node (ref "U7") (pin "5") (pinfunction "VOUT_5") (pintype "power_in"))
    )
    (net (code "31") (name "3V3_REF2") (class "Default")
      (node (ref "C12") (pin "1") (pinfunction "1_1") (pintype "passive"))
      (node (ref "U11") (pin "1") (pinfunction "VREF_1") (pintype "power_in"))
      (node (ref "U8") (pin "5") (pinfunction "VOUT_5") (pintype "power_in"))
    )
    (net (code "32") (name "5V") (class "Default")
      (node (ref "C10") (pin "2") (pinfunction "2_2") (pintype "passive"))
      (node (ref "C9") (pin "2") (pinfunction "2_2") (pintype "passive"))
      (node (ref "D1") (pin "1") (pinfunction "1_1") (pintype "passive"))
      (node (ref "D2") (pin "1") (pinfunction "1_1") (pintype "passive"))
      (node (ref "P10") (pin "1") (pinfunction "1_1") (pintype "passive"))
      (node (ref "P3") (pin "1") (pinfunction "VCC_1") (pintype "passive"))
      (node (ref "Q1") (pin "1") (pinfunction "G_1") (pintype "passive"))
      (node (ref "R12") (pin "2") (pinfunction "2_2") (pintype "passive"))
      (node (ref "R16") (pin "2") (pinfunction "2_2") (pintype "passive"))
      (node (ref "R17") (pin "2") (pinfunction "2_2") (pintype "passive"))
      (node (ref "TP1") (pin "1") (pinfunction "1_1") (pintype "passive"))
      (node (ref "U3") (pin "4") (pinfunction "VIN_4") (pintype "power_in"))
      (node (ref "U6") (pin "20") (pinfunction "VCC_20") (pintype "passive"))
      (node (ref "U7") (pin "3") (pinfunction "ENABLE_3") (pintype "passive"))
      (node (ref "U7") (pin "4") (pinfunction "VIN_4") (pintype "power_in"))
      (node (ref "U8") (pin "3") (pinfunction "ENABLE_3") (pintype "passive"))
      (node (ref "U8") (pin "4") (pinfunction "VIN_4") (pintype "power_in"))
    )
    (net (code "33") (name "GND") (class "Default")
      (node (ref "C1") (pin "2") (pinfunction "2_2") (pintype "passive"))
      (node (ref "C10") (pin "1") (pinfunction "1_1") (pintype "passive"))
      (node (ref "C11") (pin "2") (pinfunction "2_2") (pintype "passive"))
      (node (ref "C12") (pin "2") (pinfunction "2_2") (pintype "passive"))
      (node (ref "C13") (pin "1") (pinfunction "1_1") (pintype "passive"))
      (node (ref "C14") (pin "1") (pinfunction "1_1") (pintype "passive"))
      (node (ref "C15") (pin "1") (pinfunction "1_1") (pintype "passive"))
      (node (ref "C16") (pin "1") (pinfunction "1_1") (pintype "passive"))
      (node (ref "C17") (pin "1") (pinfunction "1_1") (pintype "passive"))
      (node (ref "C18") (pin "2") (pinfunction "2_2") (pintype "passive"))
      (node (ref "C19") (pin "1") (pinfunction "1_1") (pintype "passive"))
      (node (ref "C2") (pin "1") (pinfunction "1_1") (pintype "passive"))
      (node (ref "C20") (pin "2") (pinfunction "2_2") (pintype "passive"))
      (node (ref "C3") (pin "1") (pinfunction "1_1") (pintype "passive"))
      (node (ref "C4") (pin "2") (pinfunction "2_2") (pintype "passive"))
      (node (ref "C5") (pin "1") (pinfunction "1_1") (pintype "passive"))
      (node (ref "C6") (pin "1") (pinfunction "1_1") (pintype "passive"))
      (node (ref "C7") (pin "1") (pinfunction "1_1") (pintype "passive"))
      (node (ref "C9") (pin "1") (pinfunction "1_1") (pintype "passive"))
      (node (ref "D5") (pin "2") (pinfunction "2_2") (pintype "passive"))
      (node (ref "MH1") (pin "1") (pinfunction "1_1") (pintype "passive"))
      (node (ref "MH2") (pin "1") (pinfunction "1_1") (pintype "passive"))
      (node (ref "MH3") (pin "1") (pinfunction "1_1") (pintype "passive"))
      (node (ref "MH4") (pin "1") (pinfunction "1_1") (pintype "passive"))
      (node (ref "P1") (pin "1") (pinfunction "1_1") (pintype "passive"))
      (node (ref "P10") (pin "5") (pinfunction "5_5") (pintype "passive"))
      (node (ref "P10") (pin "6") (pinfunction "6_6") (pintype "passive"))
      (node (ref "P12") (pin "4") (pinfunction "4_4") (pintype "passive"))
      (node (ref "P2") (pin "6") (pinfunction "6_6") (pintype "passive"))
      (node (ref "P3") (pin "5") (pinfunction "GND_5") (pintype "passive"))
      (node (ref "P4") (pin "2") (pinfunction "2_2") (pintype "passive"))
      (node (ref "P5") (pin "2") (pinfunction "2_2") (pintype "passive"))
      (node (ref "P6") (pin "2") (pinfunction "2_2") (pintype "passive"))
      (node (ref "R10") (pin "2") (pinfunction "2_2") (pintype "passive"))
      (node (ref "R11") (pin "1") (pinfunction "1_1") (pintype "passive"))
      (node (ref "R12") (pin "1") (pinfunction "1_1") (pintype "passive"))
      (node (ref "R13") (pin "2") (pinfunction "2_2") (pintype "passive"))
      (node (ref "R14") (pin "1") (pinfunction "1_1") (pintype "passive"))
      (node (ref "R24") (pin "1") (pinfunction "1_1") (pintype "passive"))
      (node (ref "R25") (pin "1") (pinfunction "1_1") (pintype "passive"))
      (node (ref "R26") (pin "1") (pinfunction "1_1") (pintype "passive"))
      (node (ref "R27") (pin "1") (pinfunction "1_1") (pintype "passive"))
      (node (ref "R28") (pin "1") (pinfunction "1_1") (pintype "passive"))
      (node (ref "R29") (pin "1") (pinfunction "1_1") (pintype "passive"))
      (node (ref "R38") (pin "1") (pinfunction "1_1") (pintype "passive"))
      (node (ref "R39") (pin "1") (pinfunction "1_1") (pintype "passive"))
      (node (ref "R40") (pin "1") (pinfunction "1_1") (pintype "passive"))
      (node (ref "R41") (pin "1") (pinfunction "1_1") (pintype "passive"))
      (node (ref "R42") (pin "1") (pinfunction "1_1") (pintype "passive"))
      (node (ref "R43") (pin "1") (pinfunction "1_1") (pintype "passive"))
      (node (ref "R44") (pin "1") (pinfunction "1_1") (pintype "passive"))
      (node (ref "R45") (pin "1") (pinfunction "1_1") (pintype "passive"))
      (node (ref "R46") (pin "1") (pinfunction "1_1") (pintype "passive"))
      (node (ref "R47") (pin "1") (pinfunction "1_1") (pintype "passive"))
      (node (ref "S1") (pin "2") (pinfunction "2_2") (pintype "passive"))
      (node (ref "TP9") (pin "1") (pinfunction "1_1") (pintype "passive"))
      (node (ref "U1") (pin "3") (pinfunction "GND_3") (pintype "passive"))
      (node (ref "U10") (pin "4") (pinfunction "GND_4") (pintype "power_in"))
      (node (ref "U11") (pin "4") (pinfunction "GND_4") (pintype "power_in"))
      (node (ref "U2") (pin "2") (pinfunction "GND_2") (pintype "power_in"))
      (node (ref "U3") (pin "2") (pinfunction "GND_2") (pintype "power_in"))
      (node (ref "U4") (pin "2") (pinfunction "GND_2") (pintype "passive"))
      (node (ref "U5") (pin "21") (pinfunction "GND_21") (pintype "power_in"))
      (node (ref "U5") (pin "3") (pinfunction "GND_3") (pintype "power_in"))
      (node (ref "U5") (pin "5") (pinfunction "GND_5") (pintype "power_in"))
      (node (ref "U6") (pin "18") (pinfunction "GND_18") (pintype "passive"))
      (node (ref "U6") (pin "21") (pinfunction "GND_21") (pintype "passive"))
      (node (ref "U6") (pin "25") (pinfunction "AGND_25") (pintype "passive"))
      (node (ref "U6") (pin "26") (pinfunction "TEST_26") (pintype "passive"))
      (node (ref "U6") (pin "7") (pinfunction "GND_7") (pintype "passive"))
      (node (ref "U7") (pin "2") (pinfunction "GND_2") (pintype "power_in"))
      (node (ref "U8") (pin "2") (pinfunction "GND_2") (pintype "power_in"))
      (node (ref "U9") (pin "4") (pinfunction "GND_4") (pintype "power_in"))
    )
    (net (code "34") (name "Net-(D1-Pad2)") (class "Default")
      (node (ref "D1") (pin "2") (pinfunction "2_2") (pintype "passive"))
      (node (ref "R3") (pin "2") (pinfunction "2_2") (pintype "passive"))
    )
    (net (code "35") (name "Net-(D3-Pad1)") (class "Default")
      (node (ref "D3") (pin "1") (pinfunction "1_1") (pintype "passive"))
      (node (ref "R16") (pin "1") (pinfunction "1_1") (pintype "passive"))
    )
    (net (code "36") (name "Net-(D4-Pad1)") (class "Default")
      (node (ref "D4") (pin "1") (pinfunction "1_1") (pintype "passive"))
      (node (ref "R17") (pin "1") (pinfunction "1_1") (pintype "passive"))
    )
    (net (code "37") (name "Net-(D5-Pad1)") (class "Default")
      (node (ref "D5") (pin "1") (pinfunction "1_1") (pintype "passive"))
      (node (ref "R18") (pin "2") (pinfunction "2_2") (pintype "passive"))
    )
    (net (code "38") (name "Net-(P3-D+)") (class "Default")
      (node (ref "P3") (pin "3") (pinfunction "D+_3") (pintype "passive"))
      (node (ref "U6") (pin "15") (pinfunction "USBDP_15") (pintype "passive"))
    )
    (net (code "39") (name "Net-(P3-D-)") (class "Default")
      (node (ref "P3") (pin "2") (pinfunction "D-_2") (pintype "passive"))
      (node (ref "U6") (pin "16") (pinfunction "USBDM_16") (pintype "passive"))
    )
    (net (code "40") (name "Net-(Q1-S)") (class "Default")
      (node (ref "C4") (pin "1") (pinfunction "1_1") (pintype "passive"))
      (node (ref "D2") (pin "2") (pinfunction "2_2") (pintype "passive"))
      (node (ref "Q1") (pin "3") (pinfunction "S_3") (pintype "passive"))
      (node (ref "R9") (pin "1") (pinfunction "1_1") (pintype "passive"))
      (node (ref "U4") (pin "1") (pinfunction "VIN_1") (pintype "power_in"))
    )
    (net (code "41") (name "Net-(U1-ADR)") (class "Default")
      (node (ref "R10") (pin "1") (pinfunction "1_1") (pintype "passive"))
      (node (ref "R6") (pin "2") (pinfunction "2_2") (pintype "passive"))
      (node (ref "U1") (pin "10") (pinfunction "ADR_10") (pintype "passive"))
    )
    (net (code "42") (name "Net-(U2-ADD0)") (class "Default")
      (node (ref "R11") (pin "2") (pinfunction "2_2") (pintype "passive"))
      (node (ref "R7") (pin "1") (pinfunction "1_1") (pintype "passive"))
      (node (ref "U2") (pin "5") (pinfunction "ADD0_5") (pintype "input"))
    )
    (net (code "43") (name "Net-(U2-ADD1)") (class "Default")
      (node (ref "R14") (pin "2") (pinfunction "2_2") (pintype "passive"))
      (node (ref "R8") (pin "1") (pinfunction "1_1") (pintype "passive"))
      (node (ref "U2") (pin "3") (pinfunction "ADD1_3") (pintype "input"))
    )
    (net (code "44") (name "Net-(U3-PROG)") (class "Default")
      (node (ref "R13") (pin "1") (pinfunction "1_1") (pintype "passive"))
      (node (ref "U3") (pin "5") (pinfunction "PROG_5") (pintype "passive"))
    )
    (net (code "45") (name "Net-(U3-STAT)") (class "Default")
      (node (ref "R3") (pin "1") (pinfunction "1_1") (pintype "passive"))
      (node (ref "U3") (pin "1") (pinfunction "STAT_1") (pintype "passive"))
    )
    (net (code "46") (name "Net-(U4-EN)") (class "Default")
      (node (ref "R9") (pin "2") (pinfunction "2_2") (pintype "passive"))
      (node (ref "U4") (pin "3") (pinfunction "EN_3") (pintype "input"))
    )
    (net (code "47") (name "Net-(U5-AREF)") (class "Default")
      (node (ref "C7") (pin "2") (pinfunction "2_2") (pintype "passive"))
      (node (ref "U5") (pin "20") (pinfunction "AREF_20") (pintype "passive"))
    )
    (net (code "48") (name "Net-(U5-PB6_(PCINT6{slash}XTAL1{slash}TOSC1))") (class "Default")
      (node (ref "C13") (pin "2") (pinfunction "2_2") (pintype "passive"))
      (node (ref "R19") (pin "2") (pinfunction "2_2") (pintype "passive"))
      (node (ref "U5") (pin "7") (pinfunction "PB6_(PCINT6/XTAL1/TOSC1)_7") (pintype "bidirectional"))
      (node (ref "Y1") (pin "1") (pinfunction "OSC1_1") (pintype "passive"))
    )
    (net (code "49") (name "Net-(U5-PB7_(PCINT7{slash}XTAL2{slash}TOSC2))") (class "Default")
      (node (ref "C15") (pin "2") (pinfunction "2_2") (pintype "passive"))
      (node (ref "R19") (pin "1") (pinfunction "1_1") (pintype "passive"))
      (node (ref "U5") (pin "8") (pinfunction "PB7_(PCINT7/XTAL2/TOSC2)_8") (pintype "bidirectional"))
      (node (ref "Y1") (pin "2") (pinfunction "OSC2_2") (pintype "passive"))
    )
    (net (code "50") (name "Net-(U6-3V3_OUT)") (class "Default")
      (node (ref "C14") (pin "2") (pinfunction "2_2") (pintype "passive"))
      (node (ref "U6") (pin "17") (pinfunction "3V3_OUT_17") (pintype "passive"))
      (node (ref "U6") (pin "4") (pinfunction "VCCIO_4") (pintype "passive"))
    )
    (net (code "51") (name "Net-(U6-CBUS0)") (class "Default")
      (node (ref "D3") (pin "2") (pinfunction "2_2") (pintype "passive"))
      (node (ref "U6") (pin "23") (pinfunction "CBUS0_23") (pintype "passive"))
    )
    (net (code "52") (name "Net-(U6-CBUS1)") (class "Default")
      (node (ref "D4") (pin "2") (pinfunction "2_2") (pintype "passive"))
      (node (ref "U6") (pin "22") (pinfunction "CBUS1_22") (pintype "passive"))
    )
    (net (code "53") (name "Net-(U9-EN)") (class "Default")
      (node (ref "R23") (pin "1") (pinfunction "1_1") (pintype "passive"))
      (node (ref "U9") (pin "1") (pinfunction "EN_1") (pintype "input"))
    )
    (net (code "54") (name "Net-(U9-READY)") (class "Default")
      (node (ref "R20") (pin "1") (pinfunction "1_1") (pintype "passive"))
      (node (ref "U9") (pin "5") (pinfunction "READY_5") (pintype "passive"))
    )
    (net (code "55") (name "Net-(U10-A0)") (class "Default")
      (node (ref "R34") (pin "1") (pinfunction "1_1") (pintype "passive"))
      (node (ref "R38") (pin "2") (pinfunction "2_2") (pintype "passive"))
      (node (ref "U10") (pin "7") (pinfunction "A0_7") (pintype "passive"))
    )
    (net (code "56") (name "Net-(U10-A1)") (class "Default")
      (node (ref "R35") (pin "1") (pinfunction "1_1") (pintype "passive"))
      (node (ref "R39") (pin "2") (pinfunction "2_2") (pintype "passive"))
      (node (ref "U10") (pin "8") (pinfunction "A1_8") (pintype "passive"))
    )
    (net (code "57") (name "Net-(U11-A0)") (class "Default")
      (node (ref "R36") (pin "1") (pinfunction "1_1") (pintype "passive"))
      (node (ref "R40") (pin "2") (pinfunction "2_2") (pintype "passive"))
      (node (ref "U11") (pin "7") (pinfunction "A0_7") (pintype "passive"))
    )
    (net (code "58") (name "Net-(U11-A1)") (class "Default")
      (node (ref "R37") (pin "1") (pinfunction "1_1") (pintype "passive"))
      (node (ref "R41") (pin "2") (pinfunction "2_2") (pintype "passive"))
      (node (ref "U11") (pin "8") (pinfunction "A1_8") (pintype "passive"))
    )
    (net (code "59") (name "VBAT") (class "Default")
      (node (ref "C5") (pin "2") (pinfunction "2_2") (pintype "passive"))
      (node (ref "P1") (pin "2") (pinfunction "2_2") (pintype "passive"))
      (node (ref "Q1") (pin "2") (pinfunction "D_2") (pintype "passive"))
      (node (ref "U3") (pin "3") (pinfunction "VBAT_3") (pintype "power_in"))
    )
    (net (code "60") (name "V_BAT") (class "Default")
      (node (ref "P12") (pin "1") (pinfunction "1_1") (pintype "passive"))
      (node (ref "P4") (pin "1") (pinfunction "1_1") (pintype "passive"))
    )
    (net (code "61") (name "unconnected-(P3-ID-Pad4)") (class "Default")
      (node (ref "P3") (pin "4") (pinfunction "ID_4") (pintype "passive+no_connect"))
    )
    (net (code "62") (name "unconnected-(U1-3V3_OUT-Pad2)") (class "Default")
      (node (ref "U1") (pin "2") (pinfunction "3V3_OUT_2") (pintype "power_in+no_connect"))
    )
    (net (code "63") (name "unconnected-(U1-INT-Pad9)") (class "Default")
      (node (ref "U1") (pin "9") (pinfunction "INT_9") (pintype "output+no_connect"))
    )
    (net (code "64") (name "unconnected-(U1-PS1-Pad8)") (class "Default")
      (node (ref "U1") (pin "8") (pinfunction "PS1_8") (pintype "bidirectional+no_connect"))
    )
    (net (code "65") (name "unconnected-(U1-PSO-Pad7)") (class "Default")
      (node (ref "U1") (pin "7") (pinfunction "PSO_7") (pintype "bidirectional+no_connect"))
    )
    (net (code "66") (name "unconnected-(U4-NC-Pad4)") (class "Default")
      (node (ref "U4") (pin "4") (pinfunction "NC_4") (pintype "passive"))
    )
    (net (code "67") (name "unconnected-(U5-ADC6-Pad19)") (class "Default")
      (node (ref "U5") (pin "19") (pinfunction "ADC6_19") (pintype "input+no_connect"))
    )
    (net (code "68") (name "unconnected-(U5-ADC7-Pad22)") (class "Default")
      (node (ref "U5") (pin "22") (pinfunction "ADC7_22") (pintype "input+no_connect"))
    )
    (net (code "69") (name "unconnected-(U5-PB0_(PCINT0{slash}CLKO{slash}ICP1)-Pad12)") (class "Default")
      (node (ref "U5") (pin "12") (pinfunction "PB0_(PCINT0/CLKO/ICP1)_12") (pintype "bidirectional+no_connect"))
    )
    (net (code "70") (name "unconnected-(U5-PB1_(PCINT1{slash}OC1A)-Pad13)") (class "Default")
      (node (ref "U5") (pin "13") (pinfunction "PB1_(PCINT1/OC1A)_13") (pintype "bidirectional+no_connect"))
    )
    (net (code "71") (name "unconnected-(U5-PB2_(PCINT2{slash}~{SS}{slash}OC1B)-Pad14)") (class "Default")
      (node (ref "U5") (pin "14") (pinfunction "PB2_(PCINT2/~{SS}/OC1B)_14") (pintype "bidirectional+no_connect"))
    )
    (net (code "72") (name "unconnected-(U5-PC0_(ADC0{slash}PCINT8)-Pad23)") (class "Default")
      (node (ref "U5") (pin "23") (pinfunction "PC0_(ADC0/PCINT8)_23") (pintype "bidirectional+no_connect"))
    )
    (net (code "73") (name "unconnected-(U5-PC1_(ADC1{slash}PCINT9)-Pad24)") (class "Default")
      (node (ref "U5") (pin "24") (pinfunction "PC1_(ADC1/PCINT9)_24") (pintype "bidirectional+no_connect"))
    )
    (net (code "74") (name "unconnected-(U5-PD4_(PCINT20{slash}XCK{slash}T0)-Pad2)") (class "Default")
      (node (ref "U5") (pin "2") (pinfunction "PD4_(PCINT20/XCK/T0)_2") (pintype "bidirectional+no_connect"))
    )
    (net (code "75") (name "unconnected-(U5-PD5_(PCINT21{slash}OC0B{slash}T1)-Pad9)") (class "Default")
      (node (ref "U5") (pin "9") (pinfunction "PD5_(PCINT21/OC0B/T1)_9") (pintype "bidirectional+no_connect"))
    )
    (net (code "76") (name "unconnected-(U5-PD6_(PCINT22{slash}OC0A{slash}AIN0)-Pad10)") (class "Default")
      (node (ref "U5") (pin "10") (pinfunction "PD6_(PCINT22/OC0A/AIN0)_10") (pintype "bidirectional+no_connect"))
    )
    (net (code "77") (name "unconnected-(U5-PD7_(PCINT23{slash}AIN1)-Pad11)") (class "Default")
      (node (ref "U5") (pin "11") (pinfunction "PD7_(PCINT23/AIN1)_11") (pintype "bidirectional+no_connect"))
    )
    (net (code "78") (name "unconnected-(U6-CBUS2-Pad13)") (class "Default")
      (node (ref "U6") (pin "13") (pinfunction "CBUS2_13") (pintype "passive+no_connect"))
    )
    (net (code "79") (name "unconnected-(U6-CBUS3-Pad14)") (class "Default")
      (node (ref "U6") (pin "14") (pinfunction "CBUS3_14") (pintype "passive+no_connect"))
    )
    (net (code "80") (name "unconnected-(U6-CBUS4-Pad12)") (class "Default")
      (node (ref "U6") (pin "12") (pinfunction "CBUS4_12") (pintype "passive+no_connect"))
    )
    (net (code "81") (name "unconnected-(U6-CTS-Pad11)") (class "Default")
      (node (ref "U6") (pin "11") (pinfunction "CTS_11") (pintype "passive+no_connect"))
    )
    (net (code "82") (name "unconnected-(U6-DCD-Pad10)") (class "Default")
      (node (ref "U6") (pin "10") (pinfunction "DCD_10") (pintype "passive"))
    )
    (net (code "83") (name "unconnected-(U6-DSR-Pad9)") (class "Default")
      (node (ref "U6") (pin "9") (pinfunction "DSR_9") (pintype "passive+no_connect"))
    )
    (net (code "84") (name "unconnected-(U6-NC-Pad8)") (class "Default")
      (node (ref "U6") (pin "8") (pinfunction "NC_8") (pintype "passive+no_connect"))
    )
    (net (code "85") (name "unconnected-(U6-NC-Pad24)") (class "Default")
      (node (ref "U6") (pin "24") (pinfunction "NC_24") (pintype "passive+no_connect"))
    )
    (net (code "86") (name "unconnected-(U6-OSCI-Pad27)") (class "Default")
      (node (ref "U6") (pin "27") (pinfunction "OSCI_27") (pintype "passive+no_connect"))
    )
    (net (code "87") (name "unconnected-(U6-OSCO-Pad28)") (class "Default")
      (node (ref "U6") (pin "28") (pinfunction "OSCO_28") (pintype "passive+no_connect"))
    )
    (net (code "88") (name "unconnected-(U6-RESET-Pad19)") (class "Default")
      (node (ref "U6") (pin "19") (pinfunction "RESET_19") (pintype "passive+no_connect"))
    )
    (net (code "89") (name "unconnected-(U6-RI-Pad6)") (class "Default")
      (node (ref "U6") (pin "6") (pinfunction "RI_6") (pintype "passive+no_connect"))
    )
    (net (code "90") (name "unconnected-(U6-RTS-Pad3)") (class "Default")
      (node (ref "U6") (pin "3") (pinfunction "RTS_3") (pintype "passive+no_connect"))
    )
    (net (code "91") (name "unconnected-(U7-REF-Pad1)") (class "Default")
      (node (ref "U7") (pin "1") (pinfunction "REF_1") (pintype "passive"))
    )
    (net (code "92") (name "unconnected-(U8-REF-Pad1)") (class "Default")
      (node (ref "U8") (pin "1") (pinfunction "REF_1") (pintype "passive"))
    )
    (net (code "93") (name "unconnected-(U10-IN6-Pad10)") (class "Default")
      (node (ref "U10") (pin "10") (pinfunction "IN6_10") (pintype "input+no_connect"))
    )
    (net (code "94") (name "unconnected-(U10-IN7-Pad9)") (class "Default")
      (node (ref "U10") (pin "9") (pinfunction "IN7_9") (pintype "input+no_connect"))
    )
    (net (code "95") (name "unconnected-(U10-~{INT}-Pad6)") (class "Default")
      (node (ref "U10") (pin "6") (pinfunction "~{INT}_6") (pintype "output+no_connect"))
    )
    (net (code "96") (name "unconnected-(U11-IN6-Pad10)") (class "Default")
      (node (ref "U11") (pin "10") (pinfunction "IN6_10") (pintype "input+no_connect"))
    )
    (net (code "97") (name "unconnected-(U11-IN7-Pad9)") (class "Default")
      (node (ref "U11") (pin "9") (pinfunction "IN7_9") (pintype "input+no_connect"))
    )
    (net (code "98") (name "unconnected-(U11-~{INT}-Pad6)") (class "Default")
      (node (ref "U11") (pin "6") (pinfunction "~{INT}_6") (pintype "output+no_connect"))
    )
  )
)
